# phi-dac.net
KiCad netlist of a schematic drawn in EAGLE
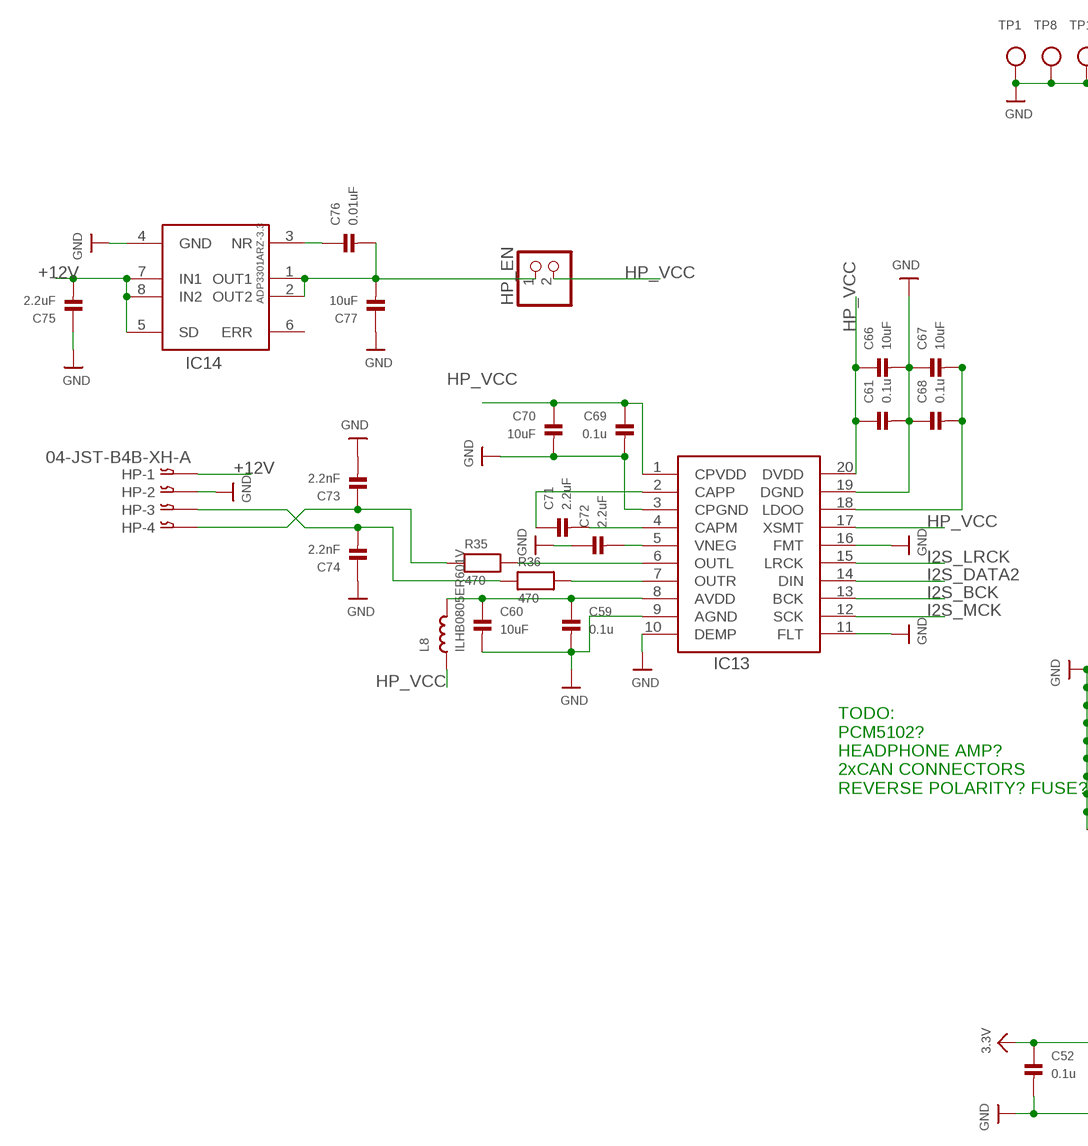
[diagram p0: schematic, sheet 1, part 1 of 2]
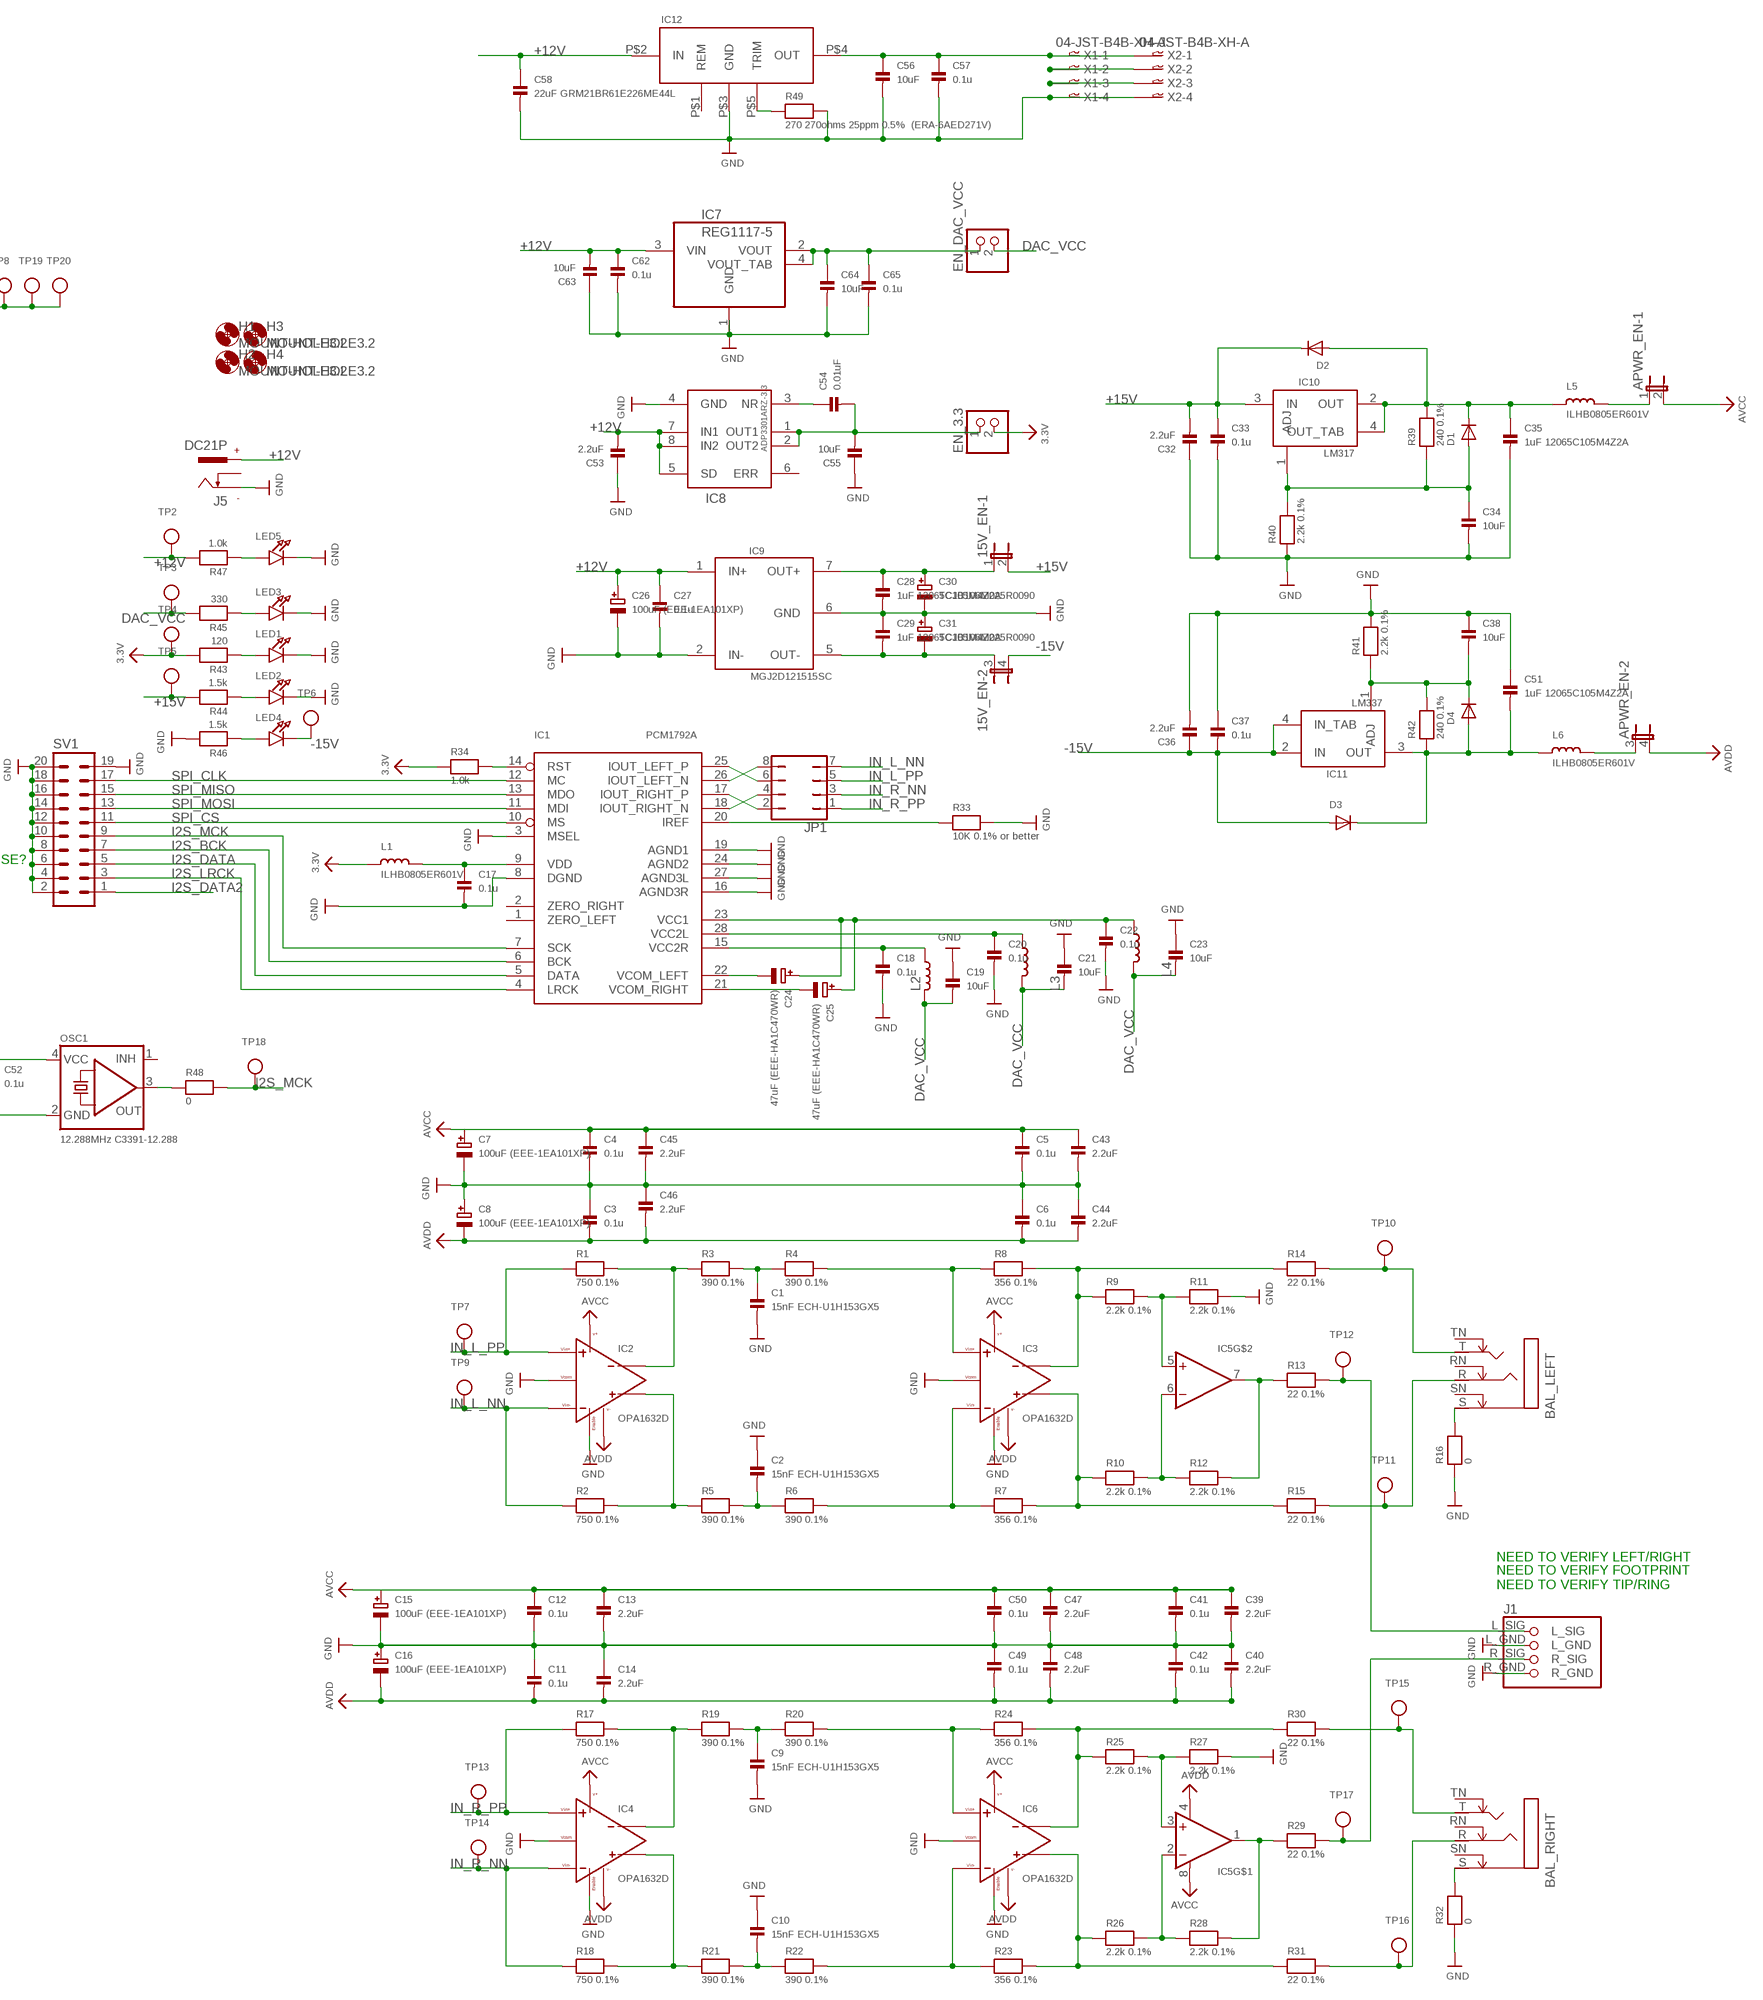
[diagram p1: schematic, sheet 1, part 2 of 2]

(export (version "E")
  (design (tool "Eeschema 10.0.6"))
  (components
    (comp (ref "15V_EN")
      (value "JP2QE")
      (footprint "eagle-import:JP2Q")
      (libsource (lib "eagle-import") (part "JP2QE"))
    )
    (comp (ref "APWR_EN")
      (value "JP2QE")
      (footprint "eagle-import:JP2Q")
      (libsource (lib "eagle-import") (part "JP2QE"))
    )
    (comp (ref "BAL_LEFT")
      (value "STEREOSW")
      (footprint "eagle-import:NMJ6HCD2")
      (libsource (lib "eagle-import") (part "STEREOSW"))
    )
    (comp (ref "BAL_RIGHT")
      (value "STEREOSW")
      (footprint "eagle-import:NMJ6HCD2")
      (libsource (lib "eagle-import") (part "STEREOSW"))
    )
    (comp (ref "C1")
      (value "15nF ECH-U1H153GX5")
      (footprint "eagle-import:1210")
      (libsource (lib "eagle-import") (part "CAP-1210"))
    )
    (comp (ref "C2")
      (value "15nF ECH-U1H153GX5")
      (footprint "eagle-import:1210")
      (libsource (lib "eagle-import") (part "CAP-1210"))
    )
    (comp (ref "C3")
      (value "0.1u")
      (footprint "eagle-import:0603")
      (libsource (lib "eagle-import") (part "CAP_CERAMIC0603"))
    )
    (comp (ref "C4")
      (value "0.1u")
      (footprint "eagle-import:0603")
      (libsource (lib "eagle-import") (part "CAP_CERAMIC0603"))
    )
    (comp (ref "C5")
      (value "0.1u")
      (footprint "eagle-import:0603")
      (libsource (lib "eagle-import") (part "CAP_CERAMIC0603"))
    )
    (comp (ref "C6")
      (value "0.1u")
      (footprint "eagle-import:0603")
      (libsource (lib "eagle-import") (part "CAP_CERAMIC0603"))
    )
    (comp (ref "C7")
      (value "100uF (EEE-1EA101XP)")
      (footprint "eagle-import:PANASONIC_D")
      (libsource (lib "eagle-import") (part "CAP_ELECTROLYTICPANASONIC_D"))
    )
    (comp (ref "C8")
      (value "100uF (EEE-1EA101XP)")
      (footprint "eagle-import:PANASONIC_D")
      (libsource (lib "eagle-import") (part "CAP_ELECTROLYTICPANASONIC_D"))
    )
    (comp (ref "C9")
      (value "15nF ECH-U1H153GX5")
      (footprint "eagle-import:1210")
      (libsource (lib "eagle-import") (part "CAP-1210"))
    )
    (comp (ref "C10")
      (value "15nF ECH-U1H153GX5")
      (footprint "eagle-import:1210")
      (libsource (lib "eagle-import") (part "CAP-1210"))
    )
    (comp (ref "C11")
      (value "0.1u")
      (footprint "eagle-import:0603")
      (libsource (lib "eagle-import") (part "CAP_CERAMIC0603"))
    )
    (comp (ref "C12")
      (value "0.1u")
      (footprint "eagle-import:0603")
      (libsource (lib "eagle-import") (part "CAP_CERAMIC0603"))
    )
    (comp (ref "C13")
      (value "2.2uF")
      (footprint "eagle-import:_0805")
      (libsource (lib "eagle-import") (part "CAP_CERAMIC_0805"))
    )
    (comp (ref "C14")
      (value "2.2uF")
      (footprint "eagle-import:_0805")
      (libsource (lib "eagle-import") (part "CAP_CERAMIC_0805"))
    )
    (comp (ref "C15")
      (value "100uF (EEE-1EA101XP)")
      (footprint "eagle-import:PANASONIC_D")
      (libsource (lib "eagle-import") (part "CAP_ELECTROLYTICPANASONIC_D"))
    )
    (comp (ref "C16")
      (value "100uF (EEE-1EA101XP)")
      (footprint "eagle-import:PANASONIC_D")
      (libsource (lib "eagle-import") (part "CAP_ELECTROLYTICPANASONIC_D"))
    )
    (comp (ref "C17")
      (value "0.1u")
      (footprint "eagle-import:0603")
      (libsource (lib "eagle-import") (part "CAP_CERAMIC0603"))
    )
    (comp (ref "C18")
      (value "0.1u")
      (footprint "eagle-import:0603")
      (libsource (lib "eagle-import") (part "CAP_CERAMIC0603"))
    )
    (comp (ref "C19")
      (value "10uF")
      (footprint "eagle-import:0805")
      (libsource (lib "eagle-import") (part "CAP_CERAMIC0805"))
    )
    (comp (ref "C20")
      (value "0.1u")
      (footprint "eagle-import:0603")
      (libsource (lib "eagle-import") (part "CAP_CERAMIC0603"))
    )
    (comp (ref "C21")
      (value "10uF")
      (footprint "eagle-import:0805")
      (libsource (lib "eagle-import") (part "CAP_CERAMIC0805"))
    )
    (comp (ref "C22")
      (value "0.1u")
      (footprint "eagle-import:0603")
      (libsource (lib "eagle-import") (part "CAP_CERAMIC0603"))
    )
    (comp (ref "C23")
      (value "10uF")
      (footprint "eagle-import:0805")
      (libsource (lib "eagle-import") (part "CAP_CERAMIC0805"))
    )
    (comp (ref "C24")
      (value "47uF (EEE-HA1C470WR)")
      (footprint "eagle-import:PANASONIC_C")
      (libsource (lib "eagle-import") (part "CAP_ELECTROLYTICPANASONIC_C"))
    )
    (comp (ref "C25")
      (value "47uF (EEE-HA1C470WR)")
      (footprint "eagle-import:PANASONIC_C")
      (libsource (lib "eagle-import") (part "CAP_ELECTROLYTICPANASONIC_C"))
    )
    (comp (ref "C26")
      (value "100uF (EEE-1EA101XP)")
      (footprint "eagle-import:PANASONIC_D")
      (libsource (lib "eagle-import") (part "CAP_ELECTROLYTICPANASONIC_D"))
    )
    (comp (ref "C27")
      (value "0.1u")
      (footprint "eagle-import:0603")
      (libsource (lib "eagle-import") (part "CAP_CERAMIC0603"))
    )
    (comp (ref "C28")
      (value "1uF 12065C105M4Z2A")
      (footprint "eagle-import:1206")
      (libsource (lib "eagle-import") (part "CAP_CERAMIC1206"))
    )
    (comp (ref "C29")
      (value "1uF 12065C105M4Z2A")
      (footprint "eagle-import:1206")
      (libsource (lib "eagle-import") (part "CAP_CERAMIC1206"))
    )
    (comp (ref "C30")
      (value "TCJB106M025R0090")
      (footprint "eagle-import:1210POL")
      (libsource (lib "eagle-import") (part "CAP-POL-1210"))
    )
    (comp (ref "C31")
      (value "TCJB106M025R0090")
      (footprint "eagle-import:1210POL")
      (libsource (lib "eagle-import") (part "CAP-POL-1210"))
    )
    (comp (ref "C32")
      (value "2.2uF")
      (footprint "eagle-import:_0805")
      (libsource (lib "eagle-import") (part "CAP_CERAMIC_0805"))
    )
    (comp (ref "C33")
      (value "0.1u")
      (footprint "eagle-import:0603")
      (libsource (lib "eagle-import") (part "CAP_CERAMIC0603"))
    )
    (comp (ref "C34")
      (value "10uF")
      (footprint "eagle-import:0805")
      (libsource (lib "eagle-import") (part "CAP_CERAMIC0805"))
    )
    (comp (ref "C35")
      (value "1uF 12065C105M4Z2A")
      (footprint "eagle-import:1206")
      (libsource (lib "eagle-import") (part "CAP_CERAMIC1206"))
    )
    (comp (ref "C36")
      (value "2.2uF")
      (footprint "eagle-import:_0805")
      (libsource (lib "eagle-import") (part "CAP_CERAMIC_0805"))
    )
    (comp (ref "C37")
      (value "0.1u")
      (footprint "eagle-import:0603")
      (libsource (lib "eagle-import") (part "CAP_CERAMIC0603"))
    )
    (comp (ref "C38")
      (value "10uF")
      (footprint "eagle-import:0805")
      (libsource (lib "eagle-import") (part "CAP_CERAMIC0805"))
    )
    (comp (ref "C39")
      (value "2.2uF")
      (footprint "eagle-import:_0805")
      (libsource (lib "eagle-import") (part "CAP_CERAMIC_0805"))
    )
    (comp (ref "C40")
      (value "2.2uF")
      (footprint "eagle-import:_0805")
      (libsource (lib "eagle-import") (part "CAP_CERAMIC_0805"))
    )
    (comp (ref "C41")
      (value "0.1u")
      (footprint "eagle-import:0603")
      (libsource (lib "eagle-import") (part "CAP_CERAMIC0603"))
    )
    (comp (ref "C42")
      (value "0.1u")
      (footprint "eagle-import:0603")
      (libsource (lib "eagle-import") (part "CAP_CERAMIC0603"))
    )
    (comp (ref "C43")
      (value "2.2uF")
      (footprint "eagle-import:_0805")
      (libsource (lib "eagle-import") (part "CAP_CERAMIC_0805"))
    )
    (comp (ref "C44")
      (value "2.2uF")
      (footprint "eagle-import:_0805")
      (libsource (lib "eagle-import") (part "CAP_CERAMIC_0805"))
    )
    (comp (ref "C45")
      (value "2.2uF")
      (footprint "eagle-import:_0805")
      (libsource (lib "eagle-import") (part "CAP_CERAMIC_0805"))
    )
    (comp (ref "C46")
      (value "2.2uF")
      (footprint "eagle-import:_0805")
      (libsource (lib "eagle-import") (part "CAP_CERAMIC_0805"))
    )
    (comp (ref "C47")
      (value "2.2uF")
      (footprint "eagle-import:_0805")
      (libsource (lib "eagle-import") (part "CAP_CERAMIC_0805"))
    )
    (comp (ref "C48")
      (value "2.2uF")
      (footprint "eagle-import:_0805")
      (libsource (lib "eagle-import") (part "CAP_CERAMIC_0805"))
    )
    (comp (ref "C49")
      (value "0.1u")
      (footprint "eagle-import:0603")
      (libsource (lib "eagle-import") (part "CAP_CERAMIC0603"))
    )
    (comp (ref "C50")
      (value "0.1u")
      (footprint "eagle-import:0603")
      (libsource (lib "eagle-import") (part "CAP_CERAMIC0603"))
    )
    (comp (ref "C51")
      (value "1uF 12065C105M4Z2A")
      (footprint "eagle-import:1206")
      (libsource (lib "eagle-import") (part "CAP_CERAMIC1206"))
    )
    (comp (ref "C52")
      (value "0.1u")
      (footprint "eagle-import:0603")
      (libsource (lib "eagle-import") (part "CAP_CERAMIC0603"))
    )
    (comp (ref "C53")
      (value "2.2uF")
      (footprint "eagle-import:_0805")
      (libsource (lib "eagle-import") (part "CAP_CERAMIC_0805"))
    )
    (comp (ref "C54")
      (value "0.01uF")
      (footprint "eagle-import:0603")
      (libsource (lib "eagle-import") (part "CAP_CERAMIC0603"))
    )
    (comp (ref "C55")
      (value "10uF")
      (footprint "eagle-import:0805")
      (libsource (lib "eagle-import") (part "CAP_CERAMIC0805"))
    )
    (comp (ref "C56")
      (value "10uF")
      (footprint "eagle-import:0805")
      (libsource (lib "eagle-import") (part "CAP_CERAMIC0805"))
    )
    (comp (ref "C57")
      (value "0.1u")
      (footprint "eagle-import:0603")
      (libsource (lib "eagle-import") (part "CAP_CERAMIC0603"))
    )
    (comp (ref "C58")
      (value "22uF GRM21BR61E226ME44L")
      (footprint "eagle-import:_0805")
      (libsource (lib "eagle-import") (part "CAP_CERAMIC_0805"))
    )
    (comp (ref "C59")
      (value "0.1u")
      (footprint "eagle-import:0603")
      (libsource (lib "eagle-import") (part "CAP_CERAMIC0603"))
    )
    (comp (ref "C60")
      (value "10uF")
      (footprint "eagle-import:0805")
      (libsource (lib "eagle-import") (part "CAP_CERAMIC0805"))
    )
    (comp (ref "C61")
      (value "0.1u")
      (footprint "eagle-import:0603")
      (libsource (lib "eagle-import") (part "CAP_CERAMIC0603"))
    )
    (comp (ref "C62")
      (value "0.1u")
      (footprint "eagle-import:0603")
      (libsource (lib "eagle-import") (part "CAP_CERAMIC0603"))
    )
    (comp (ref "C63")
      (value "10uF")
      (footprint "eagle-import:0805")
      (libsource (lib "eagle-import") (part "CAP_CERAMIC0805"))
    )
    (comp (ref "C64")
      (value "10uF")
      (footprint "eagle-import:0805")
      (libsource (lib "eagle-import") (part "CAP_CERAMIC0805"))
    )
    (comp (ref "C65")
      (value "0.1u")
      (footprint "eagle-import:0603")
      (libsource (lib "eagle-import") (part "CAP_CERAMIC0603"))
    )
    (comp (ref "C66")
      (value "10uF")
      (footprint "eagle-import:0805")
      (libsource (lib "eagle-import") (part "CAP_CERAMIC0805"))
    )
    (comp (ref "C67")
      (value "10uF")
      (footprint "eagle-import:0805")
      (libsource (lib "eagle-import") (part "CAP_CERAMIC0805"))
    )
    (comp (ref "C68")
      (value "0.1u")
      (footprint "eagle-import:0603")
      (libsource (lib "eagle-import") (part "CAP_CERAMIC0603"))
    )
    (comp (ref "C69")
      (value "0.1u")
      (footprint "eagle-import:0603")
      (libsource (lib "eagle-import") (part "CAP_CERAMIC0603"))
    )
    (comp (ref "C70")
      (value "10uF")
      (footprint "eagle-import:0805")
      (libsource (lib "eagle-import") (part "CAP_CERAMIC0805"))
    )
    (comp (ref "C71")
      (value "2.2uF")
      (footprint "eagle-import:_0805")
      (libsource (lib "eagle-import") (part "CAP_CERAMIC_0805"))
    )
    (comp (ref "C72")
      (value "2.2uF")
      (footprint "eagle-import:_0805")
      (libsource (lib "eagle-import") (part "CAP_CERAMIC_0805"))
    )
    (comp (ref "C73")
      (value "2.2nF")
      (footprint "eagle-import:_0805")
      (libsource (lib "eagle-import") (part "CAP_CERAMIC_0805"))
    )
    (comp (ref "C74")
      (value "2.2nF")
      (footprint "eagle-import:_0805")
      (libsource (lib "eagle-import") (part "CAP_CERAMIC_0805"))
    )
    (comp (ref "C75")
      (value "2.2uF")
      (footprint "eagle-import:_0805")
      (libsource (lib "eagle-import") (part "CAP_CERAMIC_0805"))
    )
    (comp (ref "C76")
      (value "0.01uF")
      (footprint "eagle-import:0603")
      (libsource (lib "eagle-import") (part "CAP_CERAMIC0603"))
    )
    (comp (ref "C77")
      (value "10uF")
      (footprint "eagle-import:0805")
      (libsource (lib "eagle-import") (part "CAP_CERAMIC0805"))
    )
    (comp (ref "D1")
      (value "DIODESOD-123")
      (footprint "eagle-import:SOD-123")
      (libsource (lib "eagle-import") (part "DIODESOD-123"))
    )
    (comp (ref "D2")
      (value "DIODESOD-123")
      (footprint "eagle-import:SOD-123")
      (libsource (lib "eagle-import") (part "DIODESOD-123"))
    )
    (comp (ref "D3")
      (value "DIODESOD-123")
      (footprint "eagle-import:SOD-123")
      (libsource (lib "eagle-import") (part "DIODESOD-123"))
    )
    (comp (ref "D4")
      (value "DIODESOD-123")
      (footprint "eagle-import:SOD-123")
      (libsource (lib "eagle-import") (part "DIODESOD-123"))
    )
    (comp (ref "EN_3.3")
      (value "HEADER-1X2")
      (footprint "eagle-import:1X02_OVAL")
      (libsource (lib "eagle-import") (part "HEADER-1X2"))
    )
    (comp (ref "EN_DAC_VCC")
      (value "HEADER-1X2")
      (footprint "eagle-import:1X02_OVAL")
      (libsource (lib "eagle-import") (part "HEADER-1X2"))
    )
    (comp (ref "H1")
      (value "MOUNT-HOLE3.2")
      (footprint "eagle-import:3,2")
      (libsource (lib "eagle-import") (part "MOUNT-HOLE3.2"))
    )
    (comp (ref "H2")
      (value "MOUNT-HOLE3.2")
      (footprint "eagle-import:3,2")
      (libsource (lib "eagle-import") (part "MOUNT-HOLE3.2"))
    )
    (comp (ref "H3")
      (value "MOUNT-HOLE3.2")
      (footprint "eagle-import:3,2")
      (libsource (lib "eagle-import") (part "MOUNT-HOLE3.2"))
    )
    (comp (ref "H4")
      (value "MOUNT-HOLE3.2")
      (footprint "eagle-import:3,2")
      (libsource (lib "eagle-import") (part "MOUNT-HOLE3.2"))
    )
    (comp (ref "HP")
      (value "04-JST-B4B-XH-A")
      (footprint "eagle-import:B4B-XH")
      (fields (field (name "MPN") "B4B-XH-A(LF)(SN)"))
      (libsource (lib "eagle-import") (part "04-JST-B4B-XH-A"))
    )
    (comp (ref "HP_EN")
      (value "HEADER-1X2")
      (footprint "eagle-import:1X02_OVAL")
      (libsource (lib "eagle-import") (part "HEADER-1X2"))
    )
    (comp (ref "IC1")
      (value "PCM1792A")
      (footprint "eagle-import:SSOP28")
      (libsource (lib "eagle-import") (part "PCM1792A"))
    )
    (comp (ref "IC2")
      (value "OPA1632D")
      (footprint "eagle-import:SO08")
      (libsource (lib "eagle-import") (part "OPA1632D"))
    )
    (comp (ref "IC3")
      (value "OPA1632D")
      (footprint "eagle-import:SO08")
      (libsource (lib "eagle-import") (part "OPA1632D"))
    )
    (comp (ref "IC4")
      (value "OPA1632D")
      (footprint "eagle-import:SO08")
      (libsource (lib "eagle-import") (part "OPA1632D"))
    )
    (comp (ref "IC5")
      (value "LM4562")
      (footprint "eagle-import:SOIC8_150MIL")
      (libsource (lib "eagle-import") (part "LM4562"))
    )
    (comp (ref "IC6")
      (value "OPA1632D")
      (footprint "eagle-import:SO08")
      (libsource (lib "eagle-import") (part "OPA1632D"))
    )
    (comp (ref "IC7")
      (value "REG1117-5")
      (footprint "eagle-import:SOT223")
      (fields (field (name "MPN") "REG1117"))
      (libsource (lib "eagle-import") (part "REG1117"))
    )
    (comp (ref "IC8")
      (value "ADP3301ARZ-3.3")
      (footprint "eagle-import:SO08")
      (libsource (lib "eagle-import") (part "ADP3301"))
    )
    (comp (ref "IC9")
      (value "MGJ2D121515SC")
      (footprint "eagle-import:MURATA-MGJ2")
      (libsource (lib "eagle-import") (part "MURATA-MGJ2"))
    )
    (comp (ref "IC10")
      (value "LM317")
      (footprint "eagle-import:SOT223")
      (libsource (lib "eagle-import") (part "LM317"))
    )
    (comp (ref "IC11")
      (value "LM337")
      (footprint "eagle-import:SOT223")
      (libsource (lib "eagle-import") (part "LM337"))
    )
    (comp (ref "IC12")
      (value "MURATA_OKR-T/10-W12-C")
      (footprint "eagle-import:MURATA_OKR-T_10-W12-C")
      (libsource (lib "eagle-import") (part "MURATA_OKR-T/10-W12-C"))
    )
    (comp (ref "IC13")
      (value "PCM5102")
      (footprint "eagle-import:TSSOP20")
      (libsource (lib "eagle-import") (part "PCM5102"))
    )
    (comp (ref "IC14")
      (value "ADP3301ARZ-3.3")
      (footprint "eagle-import:SO08")
      (libsource (lib "eagle-import") (part "ADP3301"))
    )
    (comp (ref "J1")
      (value "CUI-RCJ-2123")
      (footprint "eagle-import:CUI-RCJ-2123")
      (libsource (lib "eagle-import") (part "CUI-RCJ-2123"))
    )
    (comp (ref "J5")
      (value "DC21P")
      (footprint "eagle-import:CUI-PJ-102AH")
      (libsource (lib "eagle-import") (part "DC21P"))
    )
    (comp (ref "JP1")
      (value "JP4Q")
      (footprint "eagle-import:JP4Q")
      (libsource (lib "eagle-import") (part "JP4Q"))
    )
    (comp (ref "L1")
      (value "ILHB0805ER601V")
      (footprint "eagle-import:_0805")
      (libsource (lib "eagle-import") (part "INDUCTOR_0805"))
    )
    (comp (ref "L2")
      (value "ILHB0805ER601V")
      (footprint "eagle-import:_0805")
      (libsource (lib "eagle-import") (part "INDUCTOR_0805"))
    )
    (comp (ref "L3")
      (value "ILHB0805ER601V")
      (footprint "eagle-import:_0805")
      (libsource (lib "eagle-import") (part "INDUCTOR_0805"))
    )
    (comp (ref "L4")
      (value "ILHB0805ER601V")
      (footprint "eagle-import:_0805")
      (libsource (lib "eagle-import") (part "INDUCTOR_0805"))
    )
    (comp (ref "L5")
      (value "ILHB0805ER601V")
      (footprint "eagle-import:_0805")
      (libsource (lib "eagle-import") (part "INDUCTOR_0805"))
    )
    (comp (ref "L6")
      (value "ILHB0805ER601V")
      (footprint "eagle-import:_0805")
      (libsource (lib "eagle-import") (part "INDUCTOR_0805"))
    )
    (comp (ref "L8")
      (value "ILHB0805ER601V")
      (footprint "eagle-import:_0805")
      (libsource (lib "eagle-import") (part "INDUCTOR_0805"))
    )
    (comp (ref "LED1")
      (value "LED0805")
      (footprint "eagle-import:CHIPLED_0805")
      (libsource (lib "eagle-import") (part "LED0805"))
    )
    (comp (ref "LED2")
      (value "LED0805")
      (footprint "eagle-import:CHIPLED_0805")
      (libsource (lib "eagle-import") (part "LED0805"))
    )
    (comp (ref "LED3")
      (value "LED0805")
      (footprint "eagle-import:CHIPLED_0805")
      (libsource (lib "eagle-import") (part "LED0805"))
    )
    (comp (ref "LED4")
      (value "LED0805")
      (footprint "eagle-import:CHIPLED_0805")
      (libsource (lib "eagle-import") (part "LED0805"))
    )
    (comp (ref "LED5")
      (value "LED0805")
      (footprint "eagle-import:CHIPLED_0805")
      (libsource (lib "eagle-import") (part "LED0805"))
    )
    (comp (ref "OSC1")
      (value "12.288MHz C3391-12.288")
      (footprint "eagle-import:OSC_7X5MM")
      (libsource (lib "eagle-import") (part "OSCILLATOR"))
    )
    (comp (ref "R1")
      (value "750 0.1%")
      (footprint "eagle-import:_0805")
      (libsource (lib "eagle-import") (part "RESISTOR_0805"))
    )
    (comp (ref "R2")
      (value "750 0.1%")
      (footprint "eagle-import:_0805")
      (libsource (lib "eagle-import") (part "RESISTOR_0805"))
    )
    (comp (ref "R3")
      (value "390 0.1%")
      (footprint "eagle-import:_0805")
      (libsource (lib "eagle-import") (part "RESISTOR_0805"))
    )
    (comp (ref "R4")
      (value "390 0.1%")
      (footprint "eagle-import:_0805")
      (libsource (lib "eagle-import") (part "RESISTOR_0805"))
    )
    (comp (ref "R5")
      (value "390 0.1%")
      (footprint "eagle-import:_0805")
      (libsource (lib "eagle-import") (part "RESISTOR_0805"))
    )
    (comp (ref "R6")
      (value "390 0.1%")
      (footprint "eagle-import:_0805")
      (libsource (lib "eagle-import") (part "RESISTOR_0805"))
    )
    (comp (ref "R7")
      (value "356 0.1%")
      (footprint "eagle-import:_0805")
      (libsource (lib "eagle-import") (part "RESISTOR_0805"))
    )
    (comp (ref "R8")
      (value "356 0.1%")
      (footprint "eagle-import:_0805")
      (libsource (lib "eagle-import") (part "RESISTOR_0805"))
    )
    (comp (ref "R9")
      (value "2.2k 0.1%")
      (footprint "eagle-import:_0805")
      (libsource (lib "eagle-import") (part "RESISTOR_0805"))
    )
    (comp (ref "R10")
      (value "2.2k 0.1%")
      (footprint "eagle-import:_0805")
      (libsource (lib "eagle-import") (part "RESISTOR_0805"))
    )
    (comp (ref "R11")
      (value "2.2k 0.1%")
      (footprint "eagle-import:_0805")
      (libsource (lib "eagle-import") (part "RESISTOR_0805"))
    )
    (comp (ref "R12")
      (value "2.2k 0.1%")
      (footprint "eagle-import:_0805")
      (libsource (lib "eagle-import") (part "RESISTOR_0805"))
    )
    (comp (ref "R13")
      (value "22 0.1%")
      (footprint "eagle-import:_0805")
      (libsource (lib "eagle-import") (part "RESISTOR_0805"))
    )
    (comp (ref "R14")
      (value "22 0.1%")
      (footprint "eagle-import:_0805")
      (libsource (lib "eagle-import") (part "RESISTOR_0805"))
    )
    (comp (ref "R15")
      (value "22 0.1%")
      (footprint "eagle-import:_0805")
      (libsource (lib "eagle-import") (part "RESISTOR_0805"))
    )
    (comp (ref "R16")
      (value "0")
      (footprint "eagle-import:_0805")
      (libsource (lib "eagle-import") (part "RESISTOR_0805"))
    )
    (comp (ref "R17")
      (value "750 0.1%")
      (footprint "eagle-import:_0805")
      (libsource (lib "eagle-import") (part "RESISTOR_0805"))
    )
    (comp (ref "R18")
      (value "750 0.1%")
      (footprint "eagle-import:_0805")
      (libsource (lib "eagle-import") (part "RESISTOR_0805"))
    )
    (comp (ref "R19")
      (value "390 0.1%")
      (footprint "eagle-import:_0805")
      (libsource (lib "eagle-import") (part "RESISTOR_0805"))
    )
    (comp (ref "R20")
      (value "390 0.1%")
      (footprint "eagle-import:_0805")
      (libsource (lib "eagle-import") (part "RESISTOR_0805"))
    )
    (comp (ref "R21")
      (value "390 0.1%")
      (footprint "eagle-import:_0805")
      (libsource (lib "eagle-import") (part "RESISTOR_0805"))
    )
    (comp (ref "R22")
      (value "390 0.1%")
      (footprint "eagle-import:_0805")
      (libsource (lib "eagle-import") (part "RESISTOR_0805"))
    )
    (comp (ref "R23")
      (value "356 0.1%")
      (footprint "eagle-import:_0805")
      (libsource (lib "eagle-import") (part "RESISTOR_0805"))
    )
    (comp (ref "R24")
      (value "356 0.1%")
      (footprint "eagle-import:_0805")
      (libsource (lib "eagle-import") (part "RESISTOR_0805"))
    )
    (comp (ref "R25")
      (value "2.2k 0.1%")
      (footprint "eagle-import:_0805")
      (libsource (lib "eagle-import") (part "RESISTOR_0805"))
    )
    (comp (ref "R26")
      (value "2.2k 0.1%")
      (footprint "eagle-import:_0805")
      (libsource (lib "eagle-import") (part "RESISTOR_0805"))
    )
    (comp (ref "R27")
      (value "2.2k 0.1%")
      (footprint "eagle-import:_0805")
      (libsource (lib "eagle-import") (part "RESISTOR_0805"))
    )
    (comp (ref "R28")
      (value "2.2k 0.1%")
      (footprint "eagle-import:_0805")
      (libsource (lib "eagle-import") (part "RESISTOR_0805"))
    )
    (comp (ref "R29")
      (value "22 0.1%")
      (footprint "eagle-import:_0805")
      (libsource (lib "eagle-import") (part "RESISTOR_0805"))
    )
    (comp (ref "R30")
      (value "22 0.1%")
      (footprint "eagle-import:_0805")
      (libsource (lib "eagle-import") (part "RESISTOR_0805"))
    )
    (comp (ref "R31")
      (value "22 0.1%")
      (footprint "eagle-import:_0805")
      (libsource (lib "eagle-import") (part "RESISTOR_0805"))
    )
    (comp (ref "R32")
      (value "0")
      (footprint "eagle-import:_0805")
      (libsource (lib "eagle-import") (part "RESISTOR_0805"))
    )
    (comp (ref "R33")
      (value "10K 0.1% or better")
      (footprint "eagle-import:_0805")
      (libsource (lib "eagle-import") (part "RESISTOR_0805"))
    )
    (comp (ref "R34")
      (value "1.0k")
      (footprint "eagle-import:_0805")
      (libsource (lib "eagle-import") (part "RESISTOR_0805"))
    )
    (comp (ref "R35")
      (value "470")
      (footprint "eagle-import:_0805")
      (libsource (lib "eagle-import") (part "RESISTOR_0805"))
    )
    (comp (ref "R36")
      (value "470")
      (footprint "eagle-import:_0805")
      (libsource (lib "eagle-import") (part "RESISTOR_0805"))
    )
    (comp (ref "R39")
      (value "240 0.1%")
      (footprint "eagle-import:_0805")
      (libsource (lib "eagle-import") (part "RESISTOR_0805"))
    )
    (comp (ref "R40")
      (value "2.2k 0.1%")
      (footprint "eagle-import:_0805")
      (libsource (lib "eagle-import") (part "RESISTOR_0805"))
    )
    (comp (ref "R41")
      (value "2.2k 0.1%")
      (footprint "eagle-import:_0805")
      (libsource (lib "eagle-import") (part "RESISTOR_0805"))
    )
    (comp (ref "R42")
      (value "240 0.1%")
      (footprint "eagle-import:_0805")
      (libsource (lib "eagle-import") (part "RESISTOR_0805"))
    )
    (comp (ref "R43")
      (value "120")
      (footprint "eagle-import:_0805")
      (libsource (lib "eagle-import") (part "RESISTOR_0805"))
    )
    (comp (ref "R44")
      (value "1.5k")
      (footprint "eagle-import:_0805")
      (libsource (lib "eagle-import") (part "RESISTOR_0805"))
    )
    (comp (ref "R45")
      (value "330")
      (footprint "eagle-import:_0805")
      (libsource (lib "eagle-import") (part "RESISTOR_0805"))
    )
    (comp (ref "R46")
      (value "1.5k")
      (footprint "eagle-import:_0805")
      (libsource (lib "eagle-import") (part "RESISTOR_0805"))
    )
    (comp (ref "R47")
      (value "1.0k")
      (footprint "eagle-import:_0805")
      (libsource (lib "eagle-import") (part "RESISTOR_0805"))
    )
    (comp (ref "R48")
      (value "0")
      (footprint "eagle-import:_0805")
      (libsource (lib "eagle-import") (part "RESISTOR_0805"))
    )
    (comp (ref "R49")
      (value "270 270ohms 25ppm 0.5% (ERA-6AED271V)")
      (footprint "eagle-import:_0805")
      (libsource (lib "eagle-import") (part "RESISTOR_0805"))
    )
    (comp (ref "SV1")
      (value "ML20")
      (footprint "eagle-import:ML20")
      (libsource (lib "eagle-import") (part "ML20"))
    )
    (comp (ref "TP1")
      (value "TESTPOINT0.1\"")
      (footprint "eagle-import:1X01_ROUND")
      (libsource (lib "eagle-import") (part "TESTPOINT0.1{dblquote}"))
    )
    (comp (ref "TP2")
      (value "TESTPOINT0.1\"")
      (footprint "eagle-import:1X01_ROUND")
      (libsource (lib "eagle-import") (part "TESTPOINT0.1{dblquote}"))
    )
    (comp (ref "TP3")
      (value "TESTPOINT0.1\"")
      (footprint "eagle-import:1X01_ROUND")
      (libsource (lib "eagle-import") (part "TESTPOINT0.1{dblquote}"))
    )
    (comp (ref "TP4")
      (value "TESTPOINT0.1\"")
      (footprint "eagle-import:1X01_ROUND")
      (libsource (lib "eagle-import") (part "TESTPOINT0.1{dblquote}"))
    )
    (comp (ref "TP5")
      (value "TESTPOINT0.1\"")
      (footprint "eagle-import:1X01_ROUND")
      (libsource (lib "eagle-import") (part "TESTPOINT0.1{dblquote}"))
    )
    (comp (ref "TP6")
      (value "TESTPOINT0.1\"")
      (footprint "eagle-import:1X01_ROUND")
      (libsource (lib "eagle-import") (part "TESTPOINT0.1{dblquote}"))
    )
    (comp (ref "TP7")
      (value "TESTPOINT0.1\"")
      (footprint "eagle-import:1X01_ROUND")
      (libsource (lib "eagle-import") (part "TESTPOINT0.1{dblquote}"))
    )
    (comp (ref "TP8")
      (value "TESTPOINT0.1\"")
      (footprint "eagle-import:1X01_ROUND")
      (libsource (lib "eagle-import") (part "TESTPOINT0.1{dblquote}"))
    )
    (comp (ref "TP9")
      (value "TESTPOINT0.1\"")
      (footprint "eagle-import:1X01_ROUND")
      (libsource (lib "eagle-import") (part "TESTPOINT0.1{dblquote}"))
    )
    (comp (ref "TP10")
      (value "TESTPOINT0.1\"")
      (footprint "eagle-import:1X01_ROUND")
      (libsource (lib "eagle-import") (part "TESTPOINT0.1{dblquote}"))
    )
    (comp (ref "TP11")
      (value "TESTPOINT0.1\"")
      (footprint "eagle-import:1X01_ROUND")
      (libsource (lib "eagle-import") (part "TESTPOINT0.1{dblquote}"))
    )
    (comp (ref "TP12")
      (value "TESTPOINT0.1\"")
      (footprint "eagle-import:1X01_ROUND")
      (libsource (lib "eagle-import") (part "TESTPOINT0.1{dblquote}"))
    )
    (comp (ref "TP13")
      (value "TESTPOINT0.1\"")
      (footprint "eagle-import:1X01_ROUND")
      (libsource (lib "eagle-import") (part "TESTPOINT0.1{dblquote}"))
    )
    (comp (ref "TP14")
      (value "TESTPOINT0.1\"")
      (footprint "eagle-import:1X01_ROUND")
      (libsource (lib "eagle-import") (part "TESTPOINT0.1{dblquote}"))
    )
    (comp (ref "TP15")
      (value "TESTPOINT0.1\"")
      (footprint "eagle-import:1X01_ROUND")
      (libsource (lib "eagle-import") (part "TESTPOINT0.1{dblquote}"))
    )
    (comp (ref "TP16")
      (value "TESTPOINT0.1\"")
      (footprint "eagle-import:1X01_ROUND")
      (libsource (lib "eagle-import") (part "TESTPOINT0.1{dblquote}"))
    )
    (comp (ref "TP17")
      (value "TESTPOINT0.1\"")
      (footprint "eagle-import:1X01_ROUND")
      (libsource (lib "eagle-import") (part "TESTPOINT0.1{dblquote}"))
    )
    (comp (ref "TP18")
      (value "TESTPOINT0.1\"")
      (footprint "eagle-import:1X01_ROUND")
      (libsource (lib "eagle-import") (part "TESTPOINT0.1{dblquote}"))
    )
    (comp (ref "TP19")
      (value "TESTPOINT0.1\"")
      (footprint "eagle-import:1X01_ROUND")
      (libsource (lib "eagle-import") (part "TESTPOINT0.1{dblquote}"))
    )
    (comp (ref "TP20")
      (value "TESTPOINT0.1\"")
      (footprint "eagle-import:1X01_ROUND")
      (libsource (lib "eagle-import") (part "TESTPOINT0.1{dblquote}"))
    )
    (comp (ref "X1")
      (value "04-JST-B4B-XH-A")
      (footprint "eagle-import:B4B-XH")
      (fields (field (name "MPN") "B4B-XH-A(LF)(SN)"))
      (libsource (lib "eagle-import") (part "04-JST-B4B-XH-A"))
    )
    (comp (ref "X2")
      (value "04-JST-B4B-XH-A")
      (footprint "eagle-import:B4B-XH")
      (fields (field (name "MPN") "B4B-XH-A(LF)(SN)"))
      (libsource (lib "eagle-import") (part "04-JST-B4B-XH-A"))
    )
  )
  (nets
    (net (code "1") (name "/+12V") (class "Default")
      (node (ref "C26") (pin "+") (pinfunction "+_+") (pintype "passive"))
      (node (ref "C27") (pin "1") (pinfunction "P$1_1") (pintype "passive"))
      (node (ref "C53") (pin "2") (pinfunction "P$2_2") (pintype "passive"))
      (node (ref "C58") (pin "1") (pinfunction "P$1_1") (pintype "passive"))
      (node (ref "C62") (pin "1") (pinfunction "P$1_1") (pintype "passive"))
      (node (ref "C63") (pin "2") (pinfunction "P$2_2") (pintype "passive"))
      (node (ref "C75") (pin "2") (pinfunction "P$2_2") (pintype "passive"))
      (node (ref "HP") (pin "P$1") (pinfunction "1_P$1") (pintype "passive"))
      (node (ref "IC12") (pin "P$2") (pinfunction "IN_P$2") (pintype "bidirectional"))
      (node (ref "IC14") (pin "5") (pinfunction "SD_5") (pintype "bidirectional"))
      (node (ref "IC14") (pin "7") (pinfunction "IN1_7") (pintype "bidirectional"))
      (node (ref "IC14") (pin "8") (pinfunction "IN2_8") (pintype "bidirectional"))
      (node (ref "IC7") (pin "3") (pinfunction "VIN_3") (pintype "input"))
      (node (ref "IC8") (pin "5") (pinfunction "SD_5") (pintype "bidirectional"))
      (node (ref "IC8") (pin "7") (pinfunction "IN1_7") (pintype "bidirectional"))
      (node (ref "IC8") (pin "8") (pinfunction "IN2_8") (pintype "bidirectional"))
      (node (ref "IC9") (pin "1") (pinfunction "IN+_1") (pintype "bidirectional"))
      (node (ref "J5") (pin "+") (pinfunction "+_+") (pintype "passive"))
      (node (ref "R47") (pin "2") (pinfunction "2_2") (pintype "passive"))
      (node (ref "TP2") (pin "1") (pinfunction "P$1_1") (pintype "bidirectional"))
    )
    (net (code "2") (name "/+15V") (class "Default")
      (node (ref "15V_EN") (pin "2") (pinfunction "2_2") (pintype "passive"))
      (node (ref "C32") (pin "2") (pinfunction "P$2_2") (pintype "passive"))
      (node (ref "C33") (pin "1") (pinfunction "P$1_1") (pintype "passive"))
      (node (ref "D2") (pin "C") (pinfunction "C_C") (pintype "passive"))
      (node (ref "IC10") (pin "3") (pinfunction "IN_3") (pintype "bidirectional"))
      (node (ref "R44") (pin "2") (pinfunction "2_2") (pintype "passive"))
      (node (ref "TP5") (pin "1") (pinfunction "P$1_1") (pintype "bidirectional"))
    )
    (net (code "3") (name "/-15V") (class "Default")
      (node (ref "15V_EN") (pin "4") (pinfunction "2_4") (pintype "passive"))
      (node (ref "C36") (pin "1") (pinfunction "P$1_1") (pintype "passive"))
      (node (ref "C37") (pin "2") (pinfunction "P$2_2") (pintype "passive"))
      (node (ref "D3") (pin "A") (pinfunction "A_A") (pintype "passive"))
      (node (ref "IC11") (pin "2") (pinfunction "IN_2") (pintype "bidirectional"))
      (node (ref "IC11") (pin "4") (pinfunction "IN_TAB_4") (pintype "bidirectional"))
      (node (ref "LED4") (pin "C") (pinfunction "C_C") (pintype "passive"))
      (node (ref "TP6") (pin "1") (pinfunction "P$1_1") (pintype "bidirectional"))
    )
    (net (code "4") (name "/DAC_VCC") (class "Default")
      (node (ref "C19") (pin "2") (pinfunction "P$2_2") (pintype "passive"))
      (node (ref "C21") (pin "2") (pinfunction "P$2_2") (pintype "passive"))
      (node (ref "C23") (pin "2") (pinfunction "P$2_2") (pintype "passive"))
      (node (ref "EN_DAC_VCC") (pin "2") (pinfunction "2_2") (pintype "passive"))
      (node (ref "L2") (pin "2") (pinfunction "2_2") (pintype "passive"))
      (node (ref "L3") (pin "2") (pinfunction "2_2") (pintype "passive"))
      (node (ref "L4") (pin "2") (pinfunction "2_2") (pintype "passive"))
      (node (ref "R45") (pin "2") (pinfunction "2_2") (pintype "passive"))
      (node (ref "TP3") (pin "1") (pinfunction "P$1_1") (pintype "bidirectional"))
    )
    (net (code "5") (name "/HP_VCC") (class "Default")
      (node (ref "C61") (pin "1") (pinfunction "P$1_1") (pintype "passive"))
      (node (ref "C66") (pin "1") (pinfunction "P$1_1") (pintype "passive"))
      (node (ref "C69") (pin "1") (pinfunction "P$1_1") (pintype "passive"))
      (node (ref "C70") (pin "1") (pinfunction "P$1_1") (pintype "passive"))
      (node (ref "HP_EN") (pin "2") (pinfunction "2_2") (pintype "passive"))
      (node (ref "IC13") (pin "1") (pinfunction "CPVDD_1") (pintype "bidirectional"))
      (node (ref "IC13") (pin "17") (pinfunction "XSMT_17") (pintype "bidirectional"))
      (node (ref "IC13") (pin "20") (pinfunction "DVDD_20") (pintype "bidirectional"))
      (node (ref "L8") (pin "1") (pinfunction "1_1") (pintype "passive"))
    )
    (net (code "6") (name "/I2S_BCK") (class "Default")
      (node (ref "IC1") (pin "6") (pinfunction "BCK_6") (pintype "bidirectional"))
      (node (ref "IC13") (pin "13") (pinfunction "BCK_13") (pintype "bidirectional"))
      (node (ref "SV1") (pin "7") (pinfunction "7_7") (pintype "passive"))
    )
    (net (code "7") (name "/I2S_DATA") (class "Default")
      (node (ref "IC1") (pin "5") (pinfunction "DATA_5") (pintype "bidirectional"))
      (node (ref "SV1") (pin "5") (pinfunction "5_5") (pintype "passive"))
    )
    (net (code "8") (name "/I2S_DATA2") (class "Default")
      (node (ref "IC13") (pin "14") (pinfunction "DIN_14") (pintype "bidirectional"))
      (node (ref "SV1") (pin "1") (pinfunction "1_1") (pintype "passive"))
    )
    (net (code "9") (name "/I2S_LRCK") (class "Default")
      (node (ref "IC1") (pin "4") (pinfunction "LRCK_4") (pintype "bidirectional"))
      (node (ref "IC13") (pin "15") (pinfunction "LRCK_15") (pintype "bidirectional"))
      (node (ref "SV1") (pin "3") (pinfunction "3_3") (pintype "passive"))
    )
    (net (code "10") (name "/I2S_MCK") (class "Default")
      (node (ref "IC1") (pin "7") (pinfunction "SCK_7") (pintype "bidirectional"))
      (node (ref "IC13") (pin "12") (pinfunction "SCK_12") (pintype "bidirectional"))
      (node (ref "R48") (pin "2") (pinfunction "2_2") (pintype "passive"))
      (node (ref "SV1") (pin "9") (pinfunction "9_9") (pintype "passive"))
      (node (ref "TP18") (pin "1") (pinfunction "P$1_1") (pintype "bidirectional"))
    )
    (net (code "11") (name "/IN_L_NN") (class "Default")
      (node (ref "IC2") (pin "1") (pinfunction "VIN-_1") (pintype "bidirectional"))
      (node (ref "JP1") (pin "7") (pinfunction "7_7") (pintype "passive"))
      (node (ref "R2") (pin "1") (pinfunction "1_1") (pintype "passive"))
      (node (ref "TP9") (pin "1") (pinfunction "P$1_1") (pintype "bidirectional"))
    )
    (net (code "12") (name "/IN_L_PP") (class "Default")
      (node (ref "IC2") (pin "8") (pinfunction "VIN+_8") (pintype "bidirectional"))
      (node (ref "JP1") (pin "5") (pinfunction "5_5") (pintype "passive"))
      (node (ref "R1") (pin "1") (pinfunction "1_1") (pintype "passive"))
      (node (ref "TP7") (pin "1") (pinfunction "P$1_1") (pintype "bidirectional"))
    )
    (net (code "13") (name "/IN_R_NN") (class "Default")
      (node (ref "IC4") (pin "1") (pinfunction "VIN-_1") (pintype "bidirectional"))
      (node (ref "JP1") (pin "3") (pinfunction "3_3") (pintype "passive"))
      (node (ref "R18") (pin "1") (pinfunction "1_1") (pintype "passive"))
      (node (ref "TP14") (pin "1") (pinfunction "P$1_1") (pintype "bidirectional"))
    )
    (net (code "14") (name "/IN_R_PP") (class "Default")
      (node (ref "IC4") (pin "8") (pinfunction "VIN+_8") (pintype "bidirectional"))
      (node (ref "JP1") (pin "1") (pinfunction "1_1") (pintype "passive"))
      (node (ref "R17") (pin "1") (pinfunction "1_1") (pintype "passive"))
      (node (ref "TP13") (pin "1") (pinfunction "P$1_1") (pintype "bidirectional"))
    )
    (net (code "15") (name "/SPI_CLK") (class "Default")
      (node (ref "IC1") (pin "12") (pinfunction "MC_12") (pintype "bidirectional"))
      (node (ref "SV1") (pin "17") (pinfunction "17_17") (pintype "passive"))
    )
    (net (code "16") (name "/SPI_CS") (class "Default")
      (node (ref "IC1") (pin "10") (pinfunction "MS_10") (pintype "bidirectional"))
      (node (ref "SV1") (pin "11") (pinfunction "11_11") (pintype "passive"))
    )
    (net (code "17") (name "/SPI_MISO") (class "Default")
      (node (ref "IC1") (pin "13") (pinfunction "MDO_13") (pintype "bidirectional"))
      (node (ref "SV1") (pin "15") (pinfunction "15_15") (pintype "passive"))
    )
    (net (code "18") (name "/SPI_MOSI") (class "Default")
      (node (ref "IC1") (pin "11") (pinfunction "MDI_11") (pintype "bidirectional"))
      (node (ref "SV1") (pin "13") (pinfunction "13_13") (pintype "passive"))
    )
    (net (code "19") (name "3.3V") (class "Default")
      (node (ref "C52") (pin "1") (pinfunction "P$1_1") (pintype "passive"))
      (node (ref "EN_3.3") (pin "2") (pinfunction "2_2") (pintype "passive"))
      (node (ref "L1") (pin "1") (pinfunction "1_1") (pintype "passive"))
      (node (ref "OSC1") (pin "4") (pinfunction "VCC_4") (pintype "power_in"))
      (node (ref "R34") (pin "1") (pinfunction "1_1") (pintype "passive"))
      (node (ref "R43") (pin "2") (pinfunction "2_2") (pintype "passive"))
      (node (ref "TP4") (pin "1") (pinfunction "P$1_1") (pintype "bidirectional"))
    )
    (net (code "20") (name "AVCC") (class "Default")
      (node (ref "APWR_EN") (pin "2") (pinfunction "2_2") (pintype "passive"))
      (node (ref "C12") (pin "1") (pinfunction "P$1_1") (pintype "passive"))
      (node (ref "C13") (pin "1") (pinfunction "P$1_1") (pintype "passive"))
      (node (ref "C15") (pin "+") (pinfunction "+_+") (pintype "passive"))
      (node (ref "C39") (pin "1") (pinfunction "P$1_1") (pintype "passive"))
      (node (ref "C4") (pin "1") (pinfunction "P$1_1") (pintype "passive"))
      (node (ref "C41") (pin "1") (pinfunction "P$1_1") (pintype "passive"))
      (node (ref "C43") (pin "1") (pinfunction "P$1_1") (pintype "passive"))
      (node (ref "C45") (pin "1") (pinfunction "P$1_1") (pintype "passive"))
      (node (ref "C47") (pin "1") (pinfunction "P$1_1") (pintype "passive"))
      (node (ref "C5") (pin "1") (pinfunction "P$1_1") (pintype "passive"))
      (node (ref "C50") (pin "1") (pinfunction "P$1_1") (pintype "passive"))
      (node (ref "C7") (pin "+") (pinfunction "+_+") (pintype "passive"))
      (node (ref "IC2") (pin "3") (pinfunction "V+_3") (pintype "bidirectional"))
      (node (ref "IC3") (pin "3") (pinfunction "V+_3") (pintype "bidirectional"))
      (node (ref "IC4") (pin "3") (pinfunction "V+_3") (pintype "bidirectional"))
      (node (ref "IC5") (pin "8") (pinfunction "V+_8") (pintype "power_in"))
      (node (ref "IC6") (pin "3") (pinfunction "V+_3") (pintype "bidirectional"))
    )
    (net (code "21") (name "AVDD") (class "Default")
      (node (ref "APWR_EN") (pin "4") (pinfunction "2_4") (pintype "passive"))
      (node (ref "C11") (pin "2") (pinfunction "P$2_2") (pintype "passive"))
      (node (ref "C14") (pin "2") (pinfunction "P$2_2") (pintype "passive"))
      (node (ref "C16") (pin "-") (pinfunction "-_-") (pintype "passive"))
      (node (ref "C3") (pin "2") (pinfunction "P$2_2") (pintype "passive"))
      (node (ref "C40") (pin "2") (pinfunction "P$2_2") (pintype "passive"))
      (node (ref "C42") (pin "2") (pinfunction "P$2_2") (pintype "passive"))
      (node (ref "C44") (pin "2") (pinfunction "P$2_2") (pintype "passive"))
      (node (ref "C46") (pin "2") (pinfunction "P$2_2") (pintype "passive"))
      (node (ref "C48") (pin "2") (pinfunction "P$2_2") (pintype "passive"))
      (node (ref "C49") (pin "2") (pinfunction "P$2_2") (pintype "passive"))
      (node (ref "C6") (pin "2") (pinfunction "P$2_2") (pintype "passive"))
      (node (ref "C8") (pin "-") (pinfunction "-_-") (pintype "passive"))
      (node (ref "IC2") (pin "6") (pinfunction "V-_6") (pintype "bidirectional"))
      (node (ref "IC3") (pin "6") (pinfunction "V-_6") (pintype "bidirectional"))
      (node (ref "IC4") (pin "6") (pinfunction "V-_6") (pintype "bidirectional"))
      (node (ref "IC5") (pin "4") (pinfunction "V-_4") (pintype "power_in"))
      (node (ref "IC6") (pin "6") (pinfunction "V-_6") (pintype "bidirectional"))
    )
    (net (code "22") (name "GND") (class "Default")
      (node (ref "C1") (pin "2") (pinfunction "P$2_2") (pintype "passive"))
      (node (ref "C10") (pin "1") (pinfunction "P$1_1") (pintype "passive"))
      (node (ref "C11") (pin "1") (pinfunction "P$1_1") (pintype "passive"))
      (node (ref "C12") (pin "2") (pinfunction "P$2_2") (pintype "passive"))
      (node (ref "C13") (pin "2") (pinfunction "P$2_2") (pintype "passive"))
      (node (ref "C14") (pin "1") (pinfunction "P$1_1") (pintype "passive"))
      (node (ref "C15") (pin "-") (pinfunction "-_-") (pintype "passive"))
      (node (ref "C16") (pin "+") (pinfunction "+_+") (pintype "passive"))
      (node (ref "C17") (pin "2") (pinfunction "P$2_2") (pintype "passive"))
      (node (ref "C18") (pin "2") (pinfunction "P$2_2") (pintype "passive"))
      (node (ref "C19") (pin "1") (pinfunction "P$1_1") (pintype "passive"))
      (node (ref "C2") (pin "1") (pinfunction "P$1_1") (pintype "passive"))
      (node (ref "C20") (pin "2") (pinfunction "P$2_2") (pintype "passive"))
      (node (ref "C21") (pin "1") (pinfunction "P$1_1") (pintype "passive"))
      (node (ref "C22") (pin "2") (pinfunction "P$2_2") (pintype "passive"))
      (node (ref "C23") (pin "1") (pinfunction "P$1_1") (pintype "passive"))
      (node (ref "C26") (pin "-") (pinfunction "-_-") (pintype "passive"))
      (node (ref "C27") (pin "2") (pinfunction "P$2_2") (pintype "passive"))
      (node (ref "C28") (pin "2") (pinfunction "P$2_2") (pintype "passive"))
      (node (ref "C29") (pin "1") (pinfunction "P$1_1") (pintype "passive"))
      (node (ref "C3") (pin "1") (pinfunction "P$1_1") (pintype "passive"))
      (node (ref "C30") (pin "2-") (pinfunction "-_2-") (pintype "passive"))
      (node (ref "C31") (pin "1+") (pinfunction "+_1+") (pintype "passive"))
      (node (ref "C32") (pin "1") (pinfunction "P$1_1") (pintype "passive"))
      (node (ref "C33") (pin "2") (pinfunction "P$2_2") (pintype "passive"))
      (node (ref "C34") (pin "2") (pinfunction "P$2_2") (pintype "passive"))
      (node (ref "C35") (pin "2") (pinfunction "P$2_2") (pintype "passive"))
      (node (ref "C36") (pin "2") (pinfunction "P$2_2") (pintype "passive"))
      (node (ref "C37") (pin "1") (pinfunction "P$1_1") (pintype "passive"))
      (node (ref "C38") (pin "1") (pinfunction "P$1_1") (pintype "passive"))
      (node (ref "C39") (pin "2") (pinfunction "P$2_2") (pintype "passive"))
      (node (ref "C4") (pin "2") (pinfunction "P$2_2") (pintype "passive"))
      (node (ref "C40") (pin "1") (pinfunction "P$1_1") (pintype "passive"))
      (node (ref "C41") (pin "2") (pinfunction "P$2_2") (pintype "passive"))
      (node (ref "C42") (pin "1") (pinfunction "P$1_1") (pintype "passive"))
      (node (ref "C43") (pin "2") (pinfunction "P$2_2") (pintype "passive"))
      (node (ref "C44") (pin "1") (pinfunction "P$1_1") (pintype "passive"))
      (node (ref "C45") (pin "2") (pinfunction "P$2_2") (pintype "passive"))
      (node (ref "C46") (pin "1") (pinfunction "P$1_1") (pintype "passive"))
      (node (ref "C47") (pin "2") (pinfunction "P$2_2") (pintype "passive"))
      (node (ref "C48") (pin "1") (pinfunction "P$1_1") (pintype "passive"))
      (node (ref "C49") (pin "1") (pinfunction "P$1_1") (pintype "passive"))
      (node (ref "C5") (pin "2") (pinfunction "P$2_2") (pintype "passive"))
      (node (ref "C50") (pin "2") (pinfunction "P$2_2") (pintype "passive"))
      (node (ref "C51") (pin "1") (pinfunction "P$1_1") (pintype "passive"))
      (node (ref "C52") (pin "2") (pinfunction "P$2_2") (pintype "passive"))
      (node (ref "C53") (pin "1") (pinfunction "P$1_1") (pintype "passive"))
      (node (ref "C55") (pin "1") (pinfunction "P$1_1") (pintype "passive"))
      (node (ref "C56") (pin "2") (pinfunction "P$2_2") (pintype "passive"))
      (node (ref "C57") (pin "2") (pinfunction "P$2_2") (pintype "passive"))
      (node (ref "C58") (pin "2") (pinfunction "P$2_2") (pintype "passive"))
      (node (ref "C59") (pin "2") (pinfunction "P$2_2") (pintype "passive"))
      (node (ref "C6") (pin "1") (pinfunction "P$1_1") (pintype "passive"))
      (node (ref "C60") (pin "2") (pinfunction "P$2_2") (pintype "passive"))
      (node (ref "C61") (pin "2") (pinfunction "P$2_2") (pintype "passive"))
      (node (ref "C62") (pin "2") (pinfunction "P$2_2") (pintype "passive"))
      (node (ref "C63") (pin "1") (pinfunction "P$1_1") (pintype "passive"))
      (node (ref "C64") (pin "2") (pinfunction "P$2_2") (pintype "passive"))
      (node (ref "C65") (pin "2") (pinfunction "P$2_2") (pintype "passive"))
      (node (ref "C66") (pin "2") (pinfunction "P$2_2") (pintype "passive"))
      (node (ref "C67") (pin "1") (pinfunction "P$1_1") (pintype "passive"))
      (node (ref "C68") (pin "1") (pinfunction "P$1_1") (pintype "passive"))
      (node (ref "C69") (pin "2") (pinfunction "P$2_2") (pintype "passive"))
      (node (ref "C7") (pin "-") (pinfunction "-_-") (pintype "passive"))
      (node (ref "C70") (pin "2") (pinfunction "P$2_2") (pintype "passive"))
      (node (ref "C72") (pin "1") (pinfunction "P$1_1") (pintype "passive"))
      (node (ref "C73") (pin "2") (pinfunction "P$2_2") (pintype "passive"))
      (node (ref "C74") (pin "1") (pinfunction "P$1_1") (pintype "passive"))
      (node (ref "C75") (pin "1") (pinfunction "P$1_1") (pintype "passive"))
      (node (ref "C77") (pin "1") (pinfunction "P$1_1") (pintype "passive"))
      (node (ref "C8") (pin "+") (pinfunction "+_+") (pintype "passive"))
      (node (ref "C9") (pin "2") (pinfunction "P$2_2") (pintype "passive"))
      (node (ref "HP") (pin "P$2") (pinfunction "1_P$2") (pintype "passive"))
      (node (ref "IC1") (pin "16") (pinfunction "AGND3R_16") (pintype "bidirectional"))
      (node (ref "IC1") (pin "19") (pinfunction "AGND1_19") (pintype "bidirectional"))
      (node (ref "IC1") (pin "24") (pinfunction "AGND2_24") (pintype "bidirectional"))
      (node (ref "IC1") (pin "27") (pinfunction "AGND3L_27") (pintype "bidirectional"))
      (node (ref "IC1") (pin "3") (pinfunction "MSEL_3") (pintype "bidirectional"))
      (node (ref "IC1") (pin "8") (pinfunction "DGND_8") (pintype "bidirectional"))
      (node (ref "IC12") (pin "P$3") (pinfunction "GND_P$3") (pintype "bidirectional"))
      (node (ref "IC13") (pin "10") (pinfunction "DEMP_10") (pintype "bidirectional"))
      (node (ref "IC13") (pin "11") (pinfunction "FLT_11") (pintype "bidirectional"))
      (node (ref "IC13") (pin "16") (pinfunction "FMT_16") (pintype "bidirectional"))
      (node (ref "IC13") (pin "19") (pinfunction "DGND_19") (pintype "bidirectional"))
      (node (ref "IC13") (pin "3") (pinfunction "CPGND_3") (pintype "bidirectional"))
      (node (ref "IC13") (pin "9") (pinfunction "AGND_9") (pintype "bidirectional"))
      (node (ref "IC14") (pin "4") (pinfunction "GND_4") (pintype "bidirectional"))
      (node (ref "IC2") (pin "2") (pinfunction "VCOM_2") (pintype "bidirectional"))
      (node (ref "IC2") (pin "7") (pinfunction "ENABLE_7") (pintype "bidirectional"))
      (node (ref "IC3") (pin "2") (pinfunction "VCOM_2") (pintype "bidirectional"))
      (node (ref "IC3") (pin "7") (pinfunction "ENABLE_7") (pintype "bidirectional"))
      (node (ref "IC4") (pin "2") (pinfunction "VCOM_2") (pintype "bidirectional"))
      (node (ref "IC4") (pin "7") (pinfunction "ENABLE_7") (pintype "bidirectional"))
      (node (ref "IC6") (pin "2") (pinfunction "VCOM_2") (pintype "bidirectional"))
      (node (ref "IC6") (pin "7") (pinfunction "ENABLE_7") (pintype "bidirectional"))
      (node (ref "IC7") (pin "1") (pinfunction "GND_1") (pintype "power_in"))
      (node (ref "IC8") (pin "4") (pinfunction "GND_4") (pintype "bidirectional"))
      (node (ref "IC9") (pin "2") (pinfunction "IN-_2") (pintype "bidirectional"))
      (node (ref "IC9") (pin "6") (pinfunction "GND_6") (pintype "bidirectional"))
      (node (ref "J1") (pin "L_GND") (pinfunction "L_GND_L_GND") (pintype "passive"))
      (node (ref "J1") (pin "R_GND") (pinfunction "R_GND_R_GND") (pintype "passive"))
      (node (ref "J5") (pin "-") (pinfunction "-_-") (pintype "passive"))
      (node (ref "LED1") (pin "C") (pinfunction "C_C") (pintype "passive"))
      (node (ref "LED2") (pin "C") (pinfunction "C_C") (pintype "passive"))
      (node (ref "LED3") (pin "C") (pinfunction "C_C") (pintype "passive"))
      (node (ref "LED5") (pin "C") (pinfunction "C_C") (pintype "passive"))
      (node (ref "OSC1") (pin "2") (pinfunction "GND_2") (pintype "power_in"))
      (node (ref "R11") (pin "2") (pinfunction "2_2") (pintype "passive"))
      (node (ref "R16") (pin "1") (pinfunction "1_1") (pintype "passive"))
      (node (ref "R27") (pin "2") (pinfunction "2_2") (pintype "passive"))
      (node (ref "R32") (pin "1") (pinfunction "1_1") (pintype "passive"))
      (node (ref "R33") (pin "2") (pinfunction "2_2") (pintype "passive"))
      (node (ref "R40") (pin "1") (pinfunction "1_1") (pintype "passive"))
      (node (ref "R41") (pin "2") (pinfunction "2_2") (pintype "passive"))
      (node (ref "R46") (pin "2") (pinfunction "2_2") (pintype "passive"))
      (node (ref "R49") (pin "2") (pinfunction "2_2") (pintype "passive"))
      (node (ref "SV1") (pin "10") (pinfunction "10_10") (pintype "passive"))
      (node (ref "SV1") (pin "12") (pinfunction "12_12") (pintype "passive"))
      (node (ref "SV1") (pin "14") (pinfunction "14_14") (pintype "passive"))
      (node (ref "SV1") (pin "16") (pinfunction "16_16") (pintype "passive"))
      (node (ref "SV1") (pin "18") (pinfunction "18_18") (pintype "passive"))
      (node (ref "SV1") (pin "19") (pinfunction "19_19") (pintype "passive"))
      (node (ref "SV1") (pin "2") (pinfunction "2_2") (pintype "passive"))
      (node (ref "SV1") (pin "20") (pinfunction "20_20") (pintype "passive"))
      (node (ref "SV1") (pin "4") (pinfunction "4_4") (pintype "passive"))
      (node (ref "SV1") (pin "6") (pinfunction "6_6") (pintype "passive"))
      (node (ref "SV1") (pin "8") (pinfunction "8_8") (pintype "passive"))
      (node (ref "TP1") (pin "1") (pinfunction "P$1_1") (pintype "bidirectional"))
      (node (ref "TP19") (pin "1") (pinfunction "P$1_1") (pintype "bidirectional"))
      (node (ref "TP20") (pin "1") (pinfunction "P$1_1") (pintype "bidirectional"))
      (node (ref "TP8") (pin "1") (pinfunction "P$1_1") (pintype "bidirectional"))
      (node (ref "X1") (pin "P$4") (pinfunction "1_P$4") (pintype "passive"))
      (node (ref "X2") (pin "P$4") (pinfunction "1_P$4") (pintype "passive"))
    )
    (net (code "23") (name "Net-(15V_ENB-1)") (class "Default")
      (node (ref "15V_EN") (pin "3") (pinfunction "1_3") (pintype "passive"))
      (node (ref "C29") (pin "2") (pinfunction "P$2_2") (pintype "passive"))
      (node (ref "C31") (pin "2-") (pinfunction "-_2-") (pintype "passive"))
      (node (ref "IC9") (pin "5") (pinfunction "OUT-_5") (pintype "bidirectional"))
    )
    (net (code "24") (name "Net-(APWR_EN-Pad1)") (class "Default")
      (node (ref "APWR_EN") (pin "1") (pinfunction "1_1") (pintype "passive"))
      (node (ref "L5") (pin "2") (pinfunction "2_2") (pintype "passive"))
    )
    (net (code "25") (name "Net-(APWR_ENB-1)") (class "Default")
      (node (ref "APWR_EN") (pin "3") (pinfunction "1_3") (pintype "passive"))
      (node (ref "L6") (pin "2") (pinfunction "2_2") (pintype "passive"))
    )
    (net (code "26") (name "Net-(BAL_LEFT-PadS)") (class "Default")
      (node (ref "BAL_LEFT") (pin "S") (pinfunction "S_S") (pintype "passive"))
      (node (ref "R16") (pin "2") (pinfunction "2_2") (pintype "passive"))
    )
    (net (code "27") (name "Net-(BAL_RIGHT-PadS)") (class "Default")
      (node (ref "BAL_RIGHT") (pin "S") (pinfunction "S_S") (pintype "passive"))
      (node (ref "R32") (pin "2") (pinfunction "2_2") (pintype "passive"))
    )
    (net (code "28") (name "Net-(C1-P$1)") (class "Default")
      (node (ref "C1") (pin "1") (pinfunction "P$1_1") (pintype "passive"))
      (node (ref "R3") (pin "2") (pinfunction "2_2") (pintype "passive"))
      (node (ref "R4") (pin "1") (pinfunction "1_1") (pintype "passive"))
    )
    (net (code "29") (name "Net-(C2-P$2)") (class "Default")
      (node (ref "C2") (pin "2") (pinfunction "P$2_2") (pintype "passive"))
      (node (ref "R5") (pin "2") (pinfunction "2_2") (pintype "passive"))
      (node (ref "R6") (pin "1") (pinfunction "1_1") (pintype "passive"))
    )
    (net (code "30") (name "Net-(C9-P$1)") (class "Default")
      (node (ref "C9") (pin "1") (pinfunction "P$1_1") (pintype "passive"))
      (node (ref "R19") (pin "2") (pinfunction "2_2") (pintype "passive"))
      (node (ref "R20") (pin "1") (pinfunction "1_1") (pintype "passive"))
    )
    (net (code "31") (name "Net-(C10-P$2)") (class "Default")
      (node (ref "C10") (pin "2") (pinfunction "P$2_2") (pintype "passive"))
      (node (ref "R21") (pin "2") (pinfunction "2_2") (pintype "passive"))
      (node (ref "R22") (pin "1") (pinfunction "1_1") (pintype "passive"))
    )
    (net (code "32") (name "Net-(C17-P$1)") (class "Default")
      (node (ref "C17") (pin "1") (pinfunction "P$1_1") (pintype "passive"))
      (node (ref "IC1") (pin "9") (pinfunction "VDD_9") (pintype "bidirectional"))
      (node (ref "L1") (pin "2") (pinfunction "2_2") (pintype "passive"))
    )
    (net (code "33") (name "Net-(C18-P$1)") (class "Default")
      (node (ref "C18") (pin "1") (pinfunction "P$1_1") (pintype "passive"))
      (node (ref "IC1") (pin "15") (pinfunction "VCC2R_15") (pintype "bidirectional"))
      (node (ref "L2") (pin "1") (pinfunction "1_1") (pintype "passive"))
    )
    (net (code "34") (name "Net-(C20-P$1)") (class "Default")
      (node (ref "C20") (pin "1") (pinfunction "P$1_1") (pintype "passive"))
      (node (ref "IC1") (pin "28") (pinfunction "VCC2L_28") (pintype "bidirectional"))
      (node (ref "L3") (pin "1") (pinfunction "1_1") (pintype "passive"))
    )
    (net (code "35") (name "Net-(C22-P$1)") (class "Default")
      (node (ref "C22") (pin "1") (pinfunction "P$1_1") (pintype "passive"))
      (node (ref "C24") (pin "+") (pinfunction "+_+") (pintype "passive"))
      (node (ref "C25") (pin "+") (pinfunction "+_+") (pintype "passive"))
      (node (ref "IC1") (pin "23") (pinfunction "VCC1_23") (pintype "bidirectional"))
      (node (ref "L4") (pin "1") (pinfunction "1_1") (pintype "passive"))
    )
    (net (code "36") (name "Net-(C28-P$1)") (class "Default")
      (node (ref "15V_EN") (pin "1") (pinfunction "1_1") (pintype "passive"))
      (node (ref "C28") (pin "1") (pinfunction "P$1_1") (pintype "passive"))
      (node (ref "C30") (pin "1+") (pinfunction "+_1+") (pintype "passive"))
      (node (ref "IC9") (pin "7") (pinfunction "OUT+_7") (pintype "bidirectional"))
    )
    (net (code "37") (name "Net-(C34-P$1)") (class "Default")
      (node (ref "C34") (pin "1") (pinfunction "P$1_1") (pintype "passive"))
      (node (ref "D1") (pin "A") (pinfunction "A_A") (pintype "passive"))
      (node (ref "IC10") (pin "1") (pinfunction "ADJ_1") (pintype "bidirectional"))
      (node (ref "R39") (pin "1") (pinfunction "1_1") (pintype "passive"))
      (node (ref "R40") (pin "2") (pinfunction "2_2") (pintype "passive"))
    )
    (net (code "38") (name "Net-(C35-P$1)") (class "Default")
      (node (ref "C35") (pin "1") (pinfunction "P$1_1") (pintype "passive"))
      (node (ref "D1") (pin "C") (pinfunction "C_C") (pintype "passive"))
      (node (ref "D2") (pin "A") (pinfunction "A_A") (pintype "passive"))
      (node (ref "IC10") (pin "2") (pinfunction "OUT_2") (pintype "bidirectional"))
      (node (ref "IC10") (pin "4") (pinfunction "OUT_TAB_4") (pintype "bidirectional"))
      (node (ref "L5") (pin "1") (pinfunction "1_1") (pintype "passive"))
      (node (ref "R39") (pin "2") (pinfunction "2_2") (pintype "passive"))
    )
    (net (code "39") (name "Net-(C38-P$2)") (class "Default")
      (node (ref "C38") (pin "2") (pinfunction "P$2_2") (pintype "passive"))
      (node (ref "D4") (pin "C") (pinfunction "C_C") (pintype "passive"))
      (node (ref "IC11") (pin "1") (pinfunction "ADJ_1") (pintype "bidirectional"))
      (node (ref "R41") (pin "1") (pinfunction "1_1") (pintype "passive"))
      (node (ref "R42") (pin "2") (pinfunction "2_2") (pintype "passive"))
    )
    (net (code "40") (name "Net-(C51-P$2)") (class "Default")
      (node (ref "C51") (pin "2") (pinfunction "P$2_2") (pintype "passive"))
      (node (ref "D3") (pin "C") (pinfunction "C_C") (pintype "passive"))
      (node (ref "D4") (pin "A") (pinfunction "A_A") (pintype "passive"))
      (node (ref "IC11") (pin "3") (pinfunction "OUT_3") (pintype "bidirectional"))
      (node (ref "L6") (pin "1") (pinfunction "1_1") (pintype "passive"))
      (node (ref "R42") (pin "1") (pinfunction "1_1") (pintype "passive"))
    )
    (net (code "41") (name "Net-(C54-P$1)") (class "Default")
      (node (ref "C54") (pin "1") (pinfunction "P$1_1") (pintype "passive"))
      (node (ref "IC8") (pin "3") (pinfunction "NR_3") (pintype "bidirectional"))
    )
    (net (code "42") (name "Net-(C54-P$2)") (class "Default")
      (node (ref "C54") (pin "2") (pinfunction "P$2_2") (pintype "passive"))
      (node (ref "C55") (pin "2") (pinfunction "P$2_2") (pintype "passive"))
      (node (ref "EN_3.3") (pin "1") (pinfunction "1_1") (pintype "passive"))
      (node (ref "IC8") (pin "1") (pinfunction "OUT1_1") (pintype "bidirectional"))
      (node (ref "IC8") (pin "2") (pinfunction "OUT2_2") (pintype "bidirectional"))
    )
    (net (code "43") (name "Net-(C56-P$1)") (class "Default")
      (node (ref "C56") (pin "1") (pinfunction "P$1_1") (pintype "passive"))
      (node (ref "C57") (pin "1") (pinfunction "P$1_1") (pintype "passive"))
      (node (ref "IC12") (pin "P$4") (pinfunction "OUT_P$4") (pintype "bidirectional"))
      (node (ref "X1") (pin "P$1") (pinfunction "1_P$1") (pintype "passive"))
      (node (ref "X2") (pin "P$1") (pinfunction "1_P$1") (pintype "passive"))
    )
    (net (code "44") (name "Net-(C59-P$1)") (class "Default")
      (node (ref "C59") (pin "1") (pinfunction "P$1_1") (pintype "passive"))
      (node (ref "C60") (pin "1") (pinfunction "P$1_1") (pintype "passive"))
      (node (ref "IC13") (pin "8") (pinfunction "AVDD_8") (pintype "bidirectional"))
      (node (ref "L8") (pin "2") (pinfunction "2_2") (pintype "passive"))
    )
    (net (code "45") (name "Net-(C64-P$1)") (class "Default")
      (node (ref "C64") (pin "1") (pinfunction "P$1_1") (pintype "passive"))
      (node (ref "C65") (pin "1") (pinfunction "P$1_1") (pintype "passive"))
      (node (ref "EN_DAC_VCC") (pin "1") (pinfunction "1_1") (pintype "passive"))
      (node (ref "IC7") (pin "2") (pinfunction "VOUT_2") (pintype "output"))
      (node (ref "IC7") (pin "4") (pinfunction "VOUT_TAB_4") (pintype "output"))
    )
    (net (code "46") (name "Net-(C67-P$2)") (class "Default")
      (node (ref "C67") (pin "2") (pinfunction "P$2_2") (pintype "passive"))
      (node (ref "C68") (pin "2") (pinfunction "P$2_2") (pintype "passive"))
      (node (ref "IC13") (pin "18") (pinfunction "LDOO_18") (pintype "bidirectional"))
    )
    (net (code "47") (name "Net-(C71-P$1)") (class "Default")
      (node (ref "C71") (pin "1") (pinfunction "P$1_1") (pintype "passive"))
      (node (ref "IC13") (pin "2") (pinfunction "CAPP_2") (pintype "bidirectional"))
    )
    (net (code "48") (name "Net-(C71-P$2)") (class "Default")
      (node (ref "C71") (pin "2") (pinfunction "P$2_2") (pintype "passive"))
      (node (ref "IC13") (pin "4") (pinfunction "CAPM_4") (pintype "bidirectional"))
    )
    (net (code "49") (name "Net-(C72-P$2)") (class "Default")
      (node (ref "C72") (pin "2") (pinfunction "P$2_2") (pintype "passive"))
      (node (ref "IC13") (pin "5") (pinfunction "VNEG_5") (pintype "bidirectional"))
    )
    (net (code "50") (name "Net-(C73-P$1)") (class "Default")
      (node (ref "C73") (pin "1") (pinfunction "P$1_1") (pintype "passive"))
      (node (ref "HP") (pin "P$4") (pinfunction "1_P$4") (pintype "passive"))
      (node (ref "R35") (pin "1") (pinfunction "1_1") (pintype "passive"))
    )
    (net (code "51") (name "Net-(C74-P$2)") (class "Default")
      (node (ref "C74") (pin "2") (pinfunction "P$2_2") (pintype "passive"))
      (node (ref "HP") (pin "P$3") (pinfunction "1_P$3") (pintype "passive"))
      (node (ref "R36") (pin "1") (pinfunction "1_1") (pintype "passive"))
    )
    (net (code "52") (name "Net-(C76-P$1)") (class "Default")
      (node (ref "C76") (pin "1") (pinfunction "P$1_1") (pintype "passive"))
      (node (ref "IC14") (pin "3") (pinfunction "NR_3") (pintype "bidirectional"))
    )
    (net (code "53") (name "Net-(C76-P$2)") (class "Default")
      (node (ref "C76") (pin "2") (pinfunction "P$2_2") (pintype "passive"))
      (node (ref "C77") (pin "2") (pinfunction "P$2_2") (pintype "passive"))
      (node (ref "HP_EN") (pin "1") (pinfunction "1_1") (pintype "passive"))
      (node (ref "IC14") (pin "1") (pinfunction "OUT1_1") (pintype "bidirectional"))
      (node (ref "IC14") (pin "2") (pinfunction "OUT2_2") (pintype "bidirectional"))
    )
    (net (code "54") (name "Net-(IC1-IOUT_LEFT_N)") (class "Default")
      (node (ref "IC1") (pin "26") (pinfunction "IOUT_LEFT_N_26") (pintype "bidirectional"))
      (node (ref "JP1") (pin "8") (pinfunction "8_8") (pintype "passive"))
    )
    (net (code "55") (name "Net-(IC1-IOUT_LEFT_P)") (class "Default")
      (node (ref "IC1") (pin "25") (pinfunction "IOUT_LEFT_P_25") (pintype "bidirectional"))
      (node (ref "JP1") (pin "6") (pinfunction "6_6") (pintype "passive"))
    )
    (net (code "56") (name "Net-(IC1-IOUT_RIGHT_N)") (class "Default")
      (node (ref "IC1") (pin "18") (pinfunction "IOUT_RIGHT_N_18") (pintype "bidirectional"))
      (node (ref "JP1") (pin "4") (pinfunction "4_4") (pintype "passive"))
    )
    (net (code "57") (name "Net-(IC1-IOUT_RIGHT_P)") (class "Default")
      (node (ref "IC1") (pin "17") (pinfunction "IOUT_RIGHT_P_17") (pintype "bidirectional"))
      (node (ref "JP1") (pin "2") (pinfunction "2_2") (pintype "passive"))
    )
    (net (code "58") (name "Net-(IC1-IREF)") (class "Default")
      (node (ref "IC1") (pin "20") (pinfunction "IREF_20") (pintype "bidirectional"))
      (node (ref "R33") (pin "1") (pinfunction "1_1") (pintype "passive"))
    )
    (net (code "59") (name "Net-(IC1-RST)") (class "Default")
      (node (ref "IC1") (pin "14") (pinfunction "RST_14") (pintype "bidirectional"))
      (node (ref "R34") (pin "2") (pinfunction "2_2") (pintype "passive"))
    )
    (net (code "60") (name "Net-(IC1-VCOM_LEFT)") (class "Default")
      (node (ref "C24") (pin "-") (pinfunction "-_-") (pintype "passive"))
      (node (ref "IC1") (pin "22") (pinfunction "VCOM_LEFT_22") (pintype "bidirectional"))
    )
    (net (code "61") (name "Net-(IC1-VCOM_RIGHT)") (class "Default")
      (node (ref "C25") (pin "-") (pinfunction "-_-") (pintype "passive"))
      (node (ref "IC1") (pin "21") (pinfunction "VCOM_RIGHT_21") (pintype "bidirectional"))
    )
    (net (code "62") (name "Net-(IC2-VOUT+)") (class "Default")
      (node (ref "IC2") (pin "4") (pinfunction "VOUT+_4") (pintype "bidirectional"))
      (node (ref "R2") (pin "2") (pinfunction "2_2") (pintype "passive"))
      (node (ref "R5") (pin "1") (pinfunction "1_1") (pintype "passive"))
    )
    (net (code "63") (name "Net-(IC2-VOUT-)") (class "Default")
      (node (ref "IC2") (pin "5") (pinfunction "VOUT-_5") (pintype "bidirectional"))
      (node (ref "R1") (pin "2") (pinfunction "2_2") (pintype "passive"))
      (node (ref "R3") (pin "1") (pinfunction "1_1") (pintype "passive"))
    )
    (net (code "64") (name "Net-(IC3-VIN+)") (class "Default")
      (node (ref "IC3") (pin "8") (pinfunction "VIN+_8") (pintype "bidirectional"))
      (node (ref "R4") (pin "2") (pinfunction "2_2") (pintype "passive"))
      (node (ref "R8") (pin "1") (pinfunction "1_1") (pintype "passive"))
    )
    (net (code "65") (name "Net-(IC3-VIN-)") (class "Default")
      (node (ref "IC3") (pin "1") (pinfunction "VIN-_1") (pintype "bidirectional"))
      (node (ref "R6") (pin "2") (pinfunction "2_2") (pintype "passive"))
      (node (ref "R7") (pin "1") (pinfunction "1_1") (pintype "passive"))
    )
    (net (code "66") (name "Net-(IC3-VOUT+)") (class "Default")
      (node (ref "IC3") (pin "4") (pinfunction "VOUT+_4") (pintype "bidirectional"))
      (node (ref "R10") (pin "1") (pinfunction "1_1") (pintype "passive"))
      (node (ref "R15") (pin "1") (pinfunction "1_1") (pintype "passive"))
      (node (ref "R7") (pin "2") (pinfunction "2_2") (pintype "passive"))
    )
    (net (code "67") (name "Net-(IC3-VOUT-)") (class "Default")
      (node (ref "IC3") (pin "5") (pinfunction "VOUT-_5") (pintype "bidirectional"))
      (node (ref "R14") (pin "1") (pinfunction "1_1") (pintype "passive"))
      (node (ref "R8") (pin "2") (pinfunction "2_2") (pintype "passive"))
      (node (ref "R9") (pin "1") (pinfunction "1_1") (pintype "passive"))
    )
    (net (code "68") (name "Net-(IC4-VOUT+)") (class "Default")
      (node (ref "IC4") (pin "4") (pinfunction "VOUT+_4") (pintype "bidirectional"))
      (node (ref "R18") (pin "2") (pinfunction "2_2") (pintype "passive"))
      (node (ref "R21") (pin "1") (pinfunction "1_1") (pintype "passive"))
    )
    (net (code "69") (name "Net-(IC4-VOUT-)") (class "Default")
      (node (ref "IC4") (pin "5") (pinfunction "VOUT-_5") (pintype "bidirectional"))
      (node (ref "R17") (pin "2") (pinfunction "2_2") (pintype "passive"))
      (node (ref "R19") (pin "1") (pinfunction "1_1") (pintype "passive"))
    )
    (net (code "70") (name "Net-(IC5A-+IN)") (class "Default")
      (node (ref "IC5") (pin "3") (pinfunction "+IN_3") (pintype "input"))
      (node (ref "R25") (pin "2") (pinfunction "2_2") (pintype "passive"))
      (node (ref "R27") (pin "1") (pinfunction "1_1") (pintype "passive"))
    )
    (net (code "71") (name "Net-(IC5A--IN)") (class "Default")
      (node (ref "IC5") (pin "2") (pinfunction "-IN_2") (pintype "input"))
      (node (ref "R26") (pin "2") (pinfunction "2_2") (pintype "passive"))
      (node (ref "R28") (pin "1") (pinfunction "1_1") (pintype "passive"))
    )
    (net (code "72") (name "Net-(IC5A-OUT)") (class "Default")
      (node (ref "IC5") (pin "1") (pinfunction "OUT_1") (pintype "output"))
      (node (ref "R28") (pin "2") (pinfunction "2_2") (pintype "passive"))
      (node (ref "R29") (pin "1") (pinfunction "1_1") (pintype "passive"))
    )
    (net (code "73") (name "Net-(IC5B-+IN)") (class "Default")
      (node (ref "IC5") (pin "5") (pinfunction "+IN_5") (pintype "input"))
      (node (ref "R11") (pin "1") (pinfunction "1_1") (pintype "passive"))
      (node (ref "R9") (pin "2") (pinfunction "2_2") (pintype "passive"))
    )
    (net (code "74") (name "Net-(IC5B--IN)") (class "Default")
      (node (ref "IC5") (pin "6") (pinfunction "-IN_6") (pintype "input"))
      (node (ref "R10") (pin "2") (pinfunction "2_2") (pintype "passive"))
      (node (ref "R12") (pin "1") (pinfunction "1_1") (pintype "passive"))
    )
    (net (code "75") (name "Net-(IC5B-OUT)") (class "Default")
      (node (ref "IC5") (pin "7") (pinfunction "OUT_7") (pintype "output"))
      (node (ref "R12") (pin "2") (pinfunction "2_2") (pintype "passive"))
      (node (ref "R13") (pin "1") (pinfunction "1_1") (pintype "passive"))
    )
    (net (code "76") (name "Net-(IC6-VIN+)") (class "Default")
      (node (ref "IC6") (pin "8") (pinfunction "VIN+_8") (pintype "bidirectional"))
      (node (ref "R20") (pin "2") (pinfunction "2_2") (pintype "passive"))
      (node (ref "R24") (pin "1") (pinfunction "1_1") (pintype "passive"))
    )
    (net (code "77") (name "Net-(IC6-VIN-)") (class "Default")
      (node (ref "IC6") (pin "1") (pinfunction "VIN-_1") (pintype "bidirectional"))
      (node (ref "R22") (pin "2") (pinfunction "2_2") (pintype "passive"))
      (node (ref "R23") (pin "1") (pinfunction "1_1") (pintype "passive"))
    )
    (net (code "78") (name "Net-(IC6-VOUT+)") (class "Default")
      (node (ref "IC6") (pin "4") (pinfunction "VOUT+_4") (pintype "bidirectional"))
      (node (ref "R23") (pin "2") (pinfunction "2_2") (pintype "passive"))
      (node (ref "R26") (pin "1") (pinfunction "1_1") (pintype "passive"))
      (node (ref "R31") (pin "1") (pinfunction "1_1") (pintype "passive"))
    )
    (net (code "79") (name "Net-(IC6-VOUT-)") (class "Default")
      (node (ref "IC6") (pin "5") (pinfunction "VOUT-_5") (pintype "bidirectional"))
      (node (ref "R24") (pin "2") (pinfunction "2_2") (pintype "passive"))
      (node (ref "R25") (pin "1") (pinfunction "1_1") (pintype "passive"))
      (node (ref "R30") (pin "1") (pinfunction "1_1") (pintype "passive"))
    )
    (net (code "80") (name "Net-(IC12-TRIM)") (class "Default")
      (node (ref "IC12") (pin "P$5") (pinfunction "TRIM_P$5") (pintype "bidirectional"))
      (node (ref "R49") (pin "1") (pinfunction "1_1") (pintype "passive"))
    )
    (net (code "81") (name "Net-(IC13-OUTL)") (class "Default")
      (node (ref "IC13") (pin "6") (pinfunction "OUTL_6") (pintype "bidirectional"))
      (node (ref "R35") (pin "2") (pinfunction "2_2") (pintype "passive"))
    )
    (net (code "82") (name "Net-(IC13-OUTR)") (class "Default")
      (node (ref "IC13") (pin "7") (pinfunction "OUTR_7") (pintype "bidirectional"))
      (node (ref "R36") (pin "2") (pinfunction "2_2") (pintype "passive"))
    )
    (net (code "83") (name "Net-(LED1-PadA)") (class "Default")
      (node (ref "LED1") (pin "A") (pinfunction "A_A") (pintype "passive"))
      (node (ref "R43") (pin "1") (pinfunction "1_1") (pintype "passive"))
    )
    (net (code "84") (name "Net-(LED2-PadA)") (class "Default")
      (node (ref "LED2") (pin "A") (pinfunction "A_A") (pintype "passive"))
      (node (ref "R44") (pin "1") (pinfunction "1_1") (pintype "passive"))
    )
    (net (code "85") (name "Net-(LED3-PadA)") (class "Default")
      (node (ref "LED3") (pin "A") (pinfunction "A_A") (pintype "passive"))
      (node (ref "R45") (pin "1") (pinfunction "1_1") (pintype "passive"))
    )
    (net (code "86") (name "Net-(LED4-PadA)") (class "Default")
      (node (ref "LED4") (pin "A") (pinfunction "A_A") (pintype "passive"))
      (node (ref "R46") (pin "1") (pinfunction "1_1") (pintype "passive"))
    )
    (net (code "87") (name "Net-(LED5-PadA)") (class "Default")
      (node (ref "LED5") (pin "A") (pinfunction "A_A") (pintype "passive"))
      (node (ref "R47") (pin "1") (pinfunction "1_1") (pintype "passive"))
    )
    (net (code "88") (name "Net-(OSC1-OUT)") (class "Default")
      (node (ref "OSC1") (pin "3") (pinfunction "OUT_3") (pintype "output"))
      (node (ref "R48") (pin "1") (pinfunction "1_1") (pintype "passive"))
    )
    (net (code "89") (name "Net-(TP10-P$1)") (class "Default")
      (node (ref "BAL_LEFT") (pin "T") (pinfunction "T_T") (pintype "passive"))
      (node (ref "R14") (pin "2") (pinfunction "2_2") (pintype "passive"))
      (node (ref "TP10") (pin "1") (pinfunction "P$1_1") (pintype "bidirectional"))
    )
    (net (code "90") (name "Net-(TP11-P$1)") (class "Default")
      (node (ref "BAL_LEFT") (pin "R") (pinfunction "R_R") (pintype "passive"))
      (node (ref "R15") (pin "2") (pinfunction "2_2") (pintype "passive"))
      (node (ref "TP11") (pin "1") (pinfunction "P$1_1") (pintype "bidirectional"))
    )
    (net (code "91") (name "Net-(TP12-P$1)") (class "Default")
      (node (ref "J1") (pin "L_SIG") (pinfunction "L_SIG_L_SIG") (pintype "passive"))
      (node (ref "R13") (pin "2") (pinfunction "2_2") (pintype "passive"))
      (node (ref "TP12") (pin "1") (pinfunction "P$1_1") (pintype "bidirectional"))
    )
    (net (code "92") (name "Net-(TP15-P$1)") (class "Default")
      (node (ref "BAL_RIGHT") (pin "T") (pinfunction "T_T") (pintype "passive"))
      (node (ref "R30") (pin "2") (pinfunction "2_2") (pintype "passive"))
      (node (ref "TP15") (pin "1") (pinfunction "P$1_1") (pintype "bidirectional"))
    )
    (net (code "93") (name "Net-(TP16-P$1)") (class "Default")
      (node (ref "BAL_RIGHT") (pin "R") (pinfunction "R_R") (pintype "passive"))
      (node (ref "R31") (pin "2") (pinfunction "2_2") (pintype "passive"))
      (node (ref "TP16") (pin "1") (pinfunction "P$1_1") (pintype "bidirectional"))
    )
    (net (code "94") (name "Net-(TP17-P$1)") (class "Default")
      (node (ref "J1") (pin "R_SIG") (pinfunction "R_SIG_R_SIG") (pintype "passive"))
      (node (ref "R29") (pin "2") (pinfunction "2_2") (pintype "passive"))
      (node (ref "TP17") (pin "1") (pinfunction "P$1_1") (pintype "bidirectional"))
    )
    (net (code "95") (name "Net-(X1B-1)") (class "Default")
      (node (ref "X1") (pin "P$2") (pinfunction "1_P$2") (pintype "passive"))
      (node (ref "X2") (pin "P$2") (pinfunction "1_P$2") (pintype "passive"))
    )
    (net (code "96") (name "Net-(X1C-1)") (class "Default")
      (node (ref "X1") (pin "P$3") (pinfunction "1_P$3") (pintype "passive"))
      (node (ref "X2") (pin "P$3") (pinfunction "1_P$3") (pintype "passive"))
    )
    (net (code "97") (name "unconnected-(BAL_LEFT-PadRN)") (class "Default")
      (node (ref "BAL_LEFT") (pin "RN") (pinfunction "RN_RN") (pintype "passive"))
    )
    (net (code "98") (name "unconnected-(BAL_LEFT-PadSN)") (class "Default")
      (node (ref "BAL_LEFT") (pin "SN") (pinfunction "SN_SN") (pintype "passive"))
    )
    (net (code "99") (name "unconnected-(BAL_LEFT-PadTN)") (class "Default")
      (node (ref "BAL_LEFT") (pin "TN") (pinfunction "TN_TN") (pintype "passive"))
    )
    (net (code "100") (name "unconnected-(BAL_RIGHT-PadRN)") (class "Default")
      (node (ref "BAL_RIGHT") (pin "RN") (pinfunction "RN_RN") (pintype "passive"))
    )
    (net (code "101") (name "unconnected-(BAL_RIGHT-PadSN)") (class "Default")
      (node (ref "BAL_RIGHT") (pin "SN") (pinfunction "SN_SN") (pintype "passive"))
    )
    (net (code "102") (name "unconnected-(BAL_RIGHT-PadTN)") (class "Default")
      (node (ref "BAL_RIGHT") (pin "TN") (pinfunction "TN_TN") (pintype "passive"))
    )
    (net (code "103") (name "unconnected-(IC1-ZERO_LEFT-Pad1)") (class "Default")
      (node (ref "IC1") (pin "1") (pinfunction "ZERO_LEFT_1") (pintype "bidirectional"))
    )
    (net (code "104") (name "unconnected-(IC1-ZERO_RIGHT-Pad2)") (class "Default")
      (node (ref "IC1") (pin "2") (pinfunction "ZERO_RIGHT_2") (pintype "bidirectional"))
    )
    (net (code "105") (name "unconnected-(IC8-ERR-Pad6)") (class "Default")
      (node (ref "IC8") (pin "6") (pinfunction "ERR_6") (pintype "bidirectional"))
    )
    (net (code "106") (name "unconnected-(IC12-REM-PadP$1)") (class "Default")
      (node (ref "IC12") (pin "P$1") (pinfunction "REM_P$1") (pintype "bidirectional"))
    )
    (net (code "107") (name "unconnected-(IC14-ERR-Pad6)") (class "Default")
      (node (ref "IC14") (pin "6") (pinfunction "ERR_6") (pintype "bidirectional"))
    )
    (net (code "108") (name "unconnected-(J5-PadC)") (class "Default")
      (node (ref "J5") (pin "C") (pinfunction "C_C") (pintype "passive"))
    )
    (net (code "109") (name "unconnected-(OSC1-INH-Pad1)") (class "Default")
      (node (ref "OSC1") (pin "1") (pinfunction "INH_1") (pintype "bidirectional"))
    )
  )
)
